# ControlBoardpH.net
KiCad netlist of a schematic drawn in EAGLE
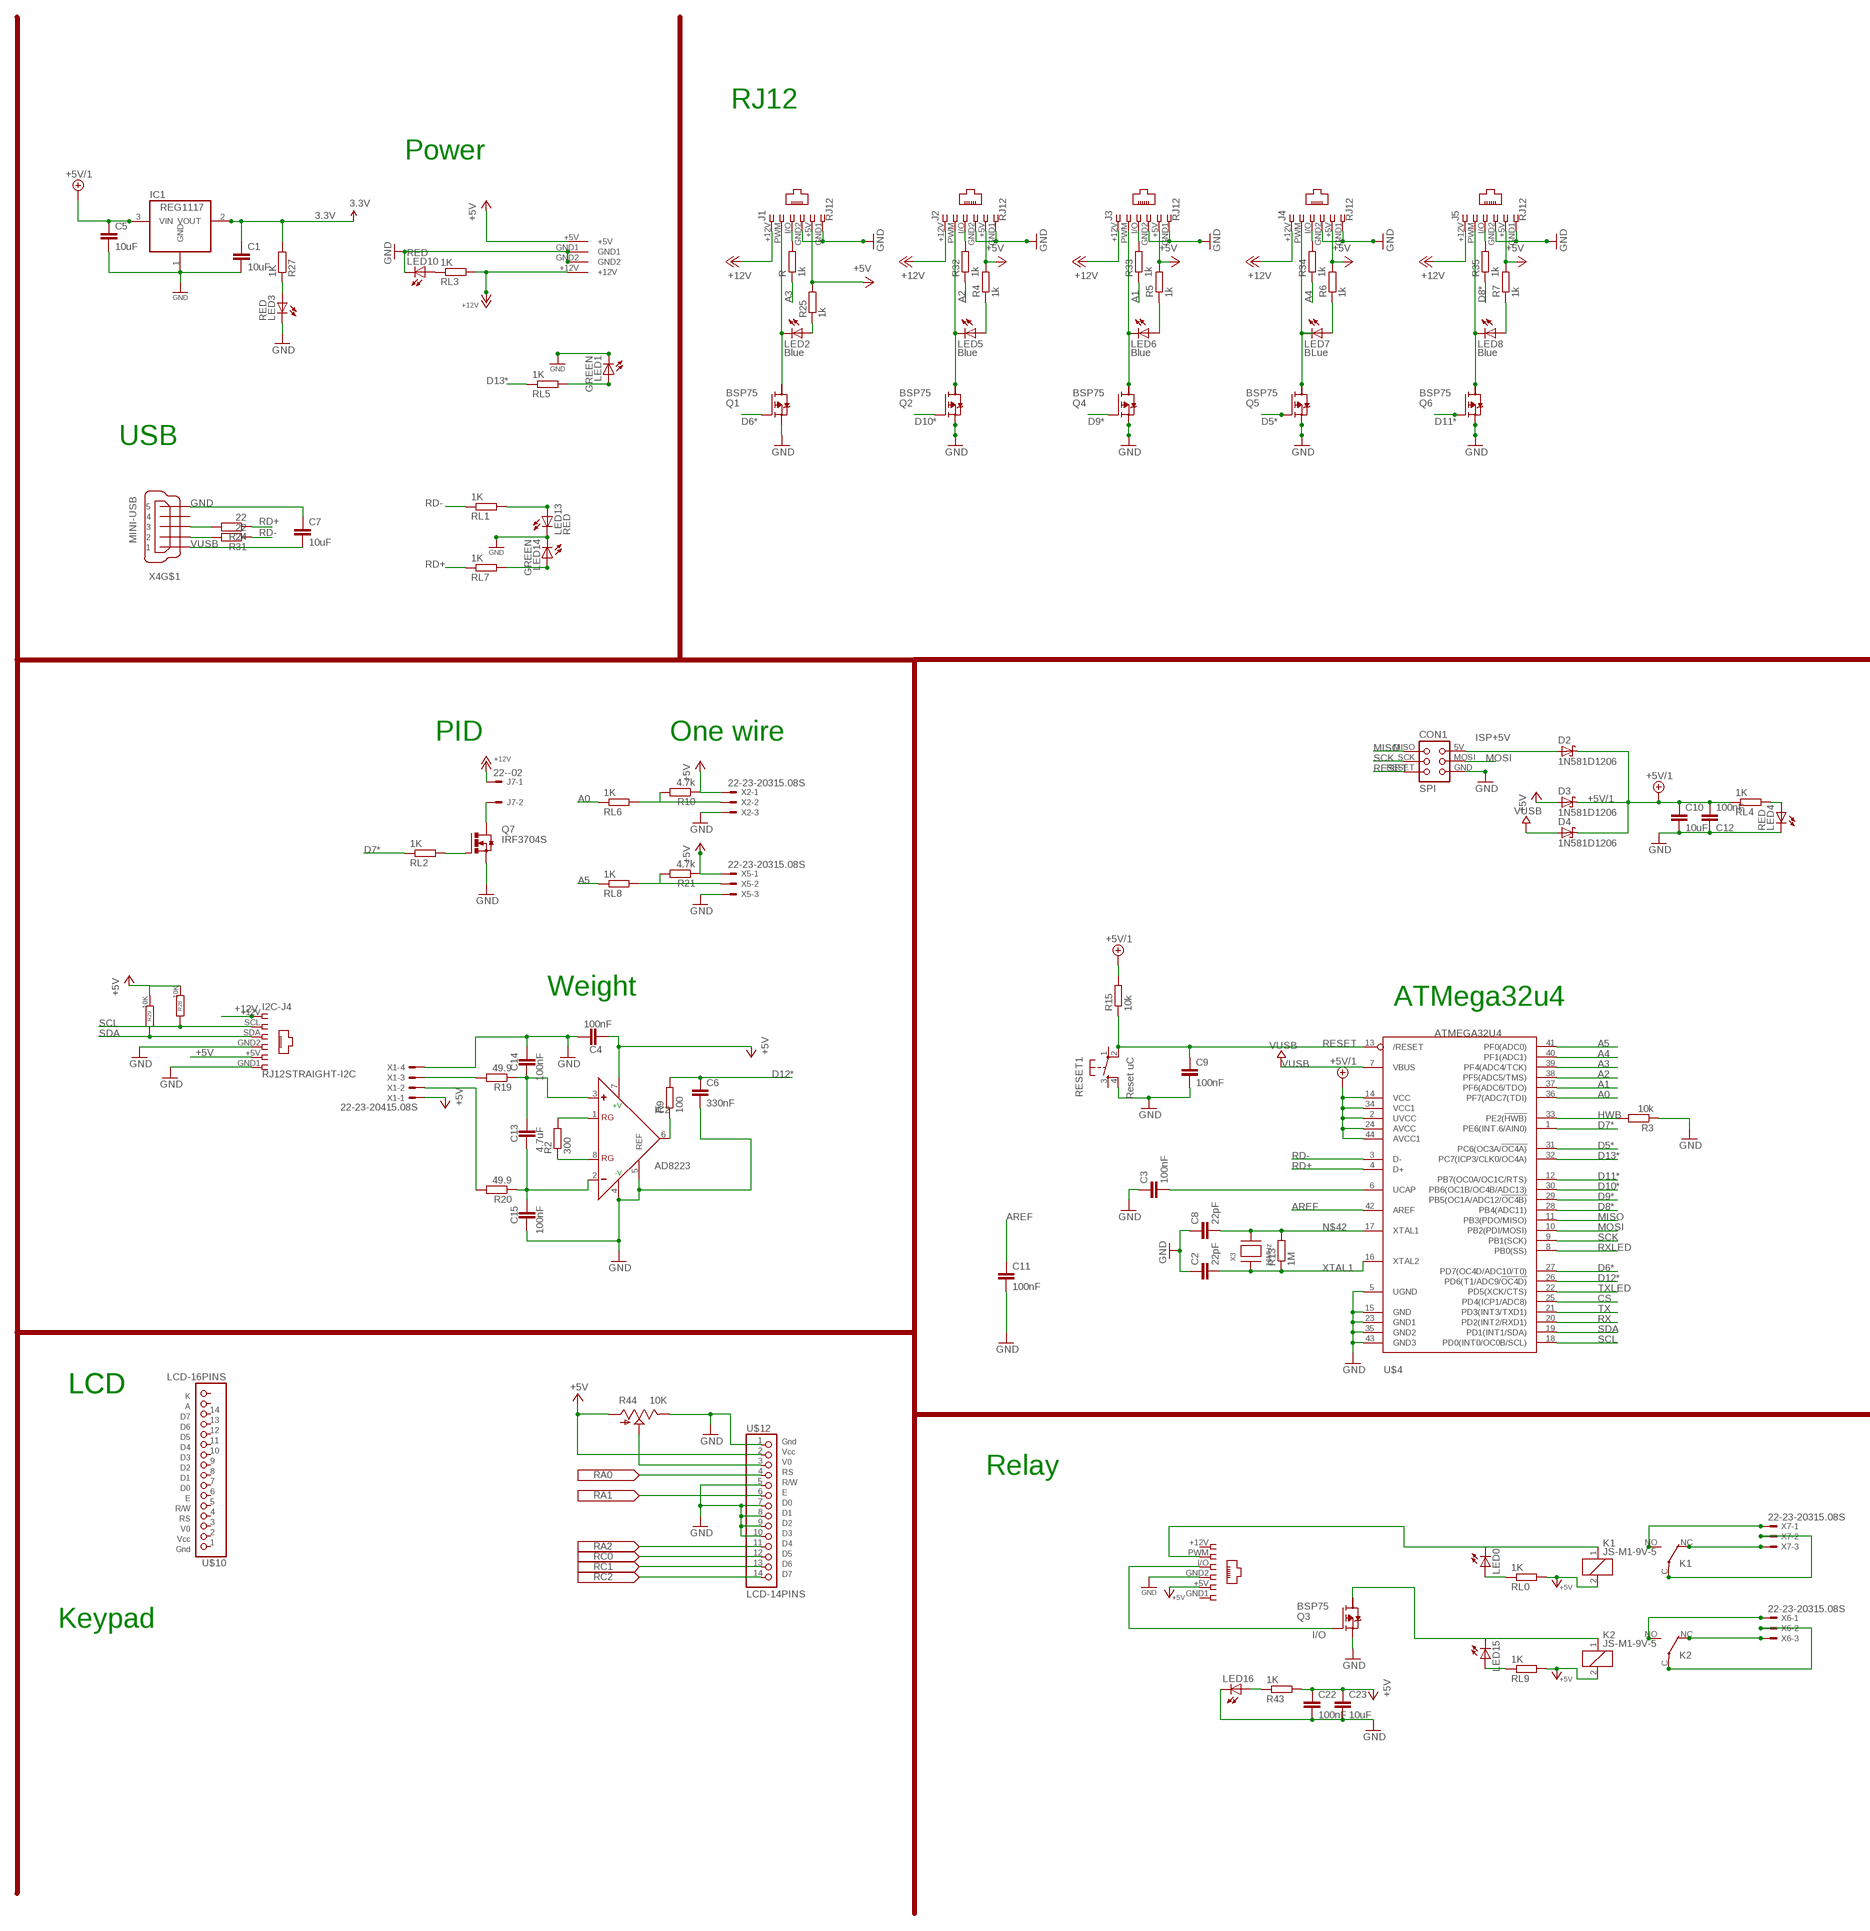
[diagram p0: schematic, sheet 1, part 1 of 2]
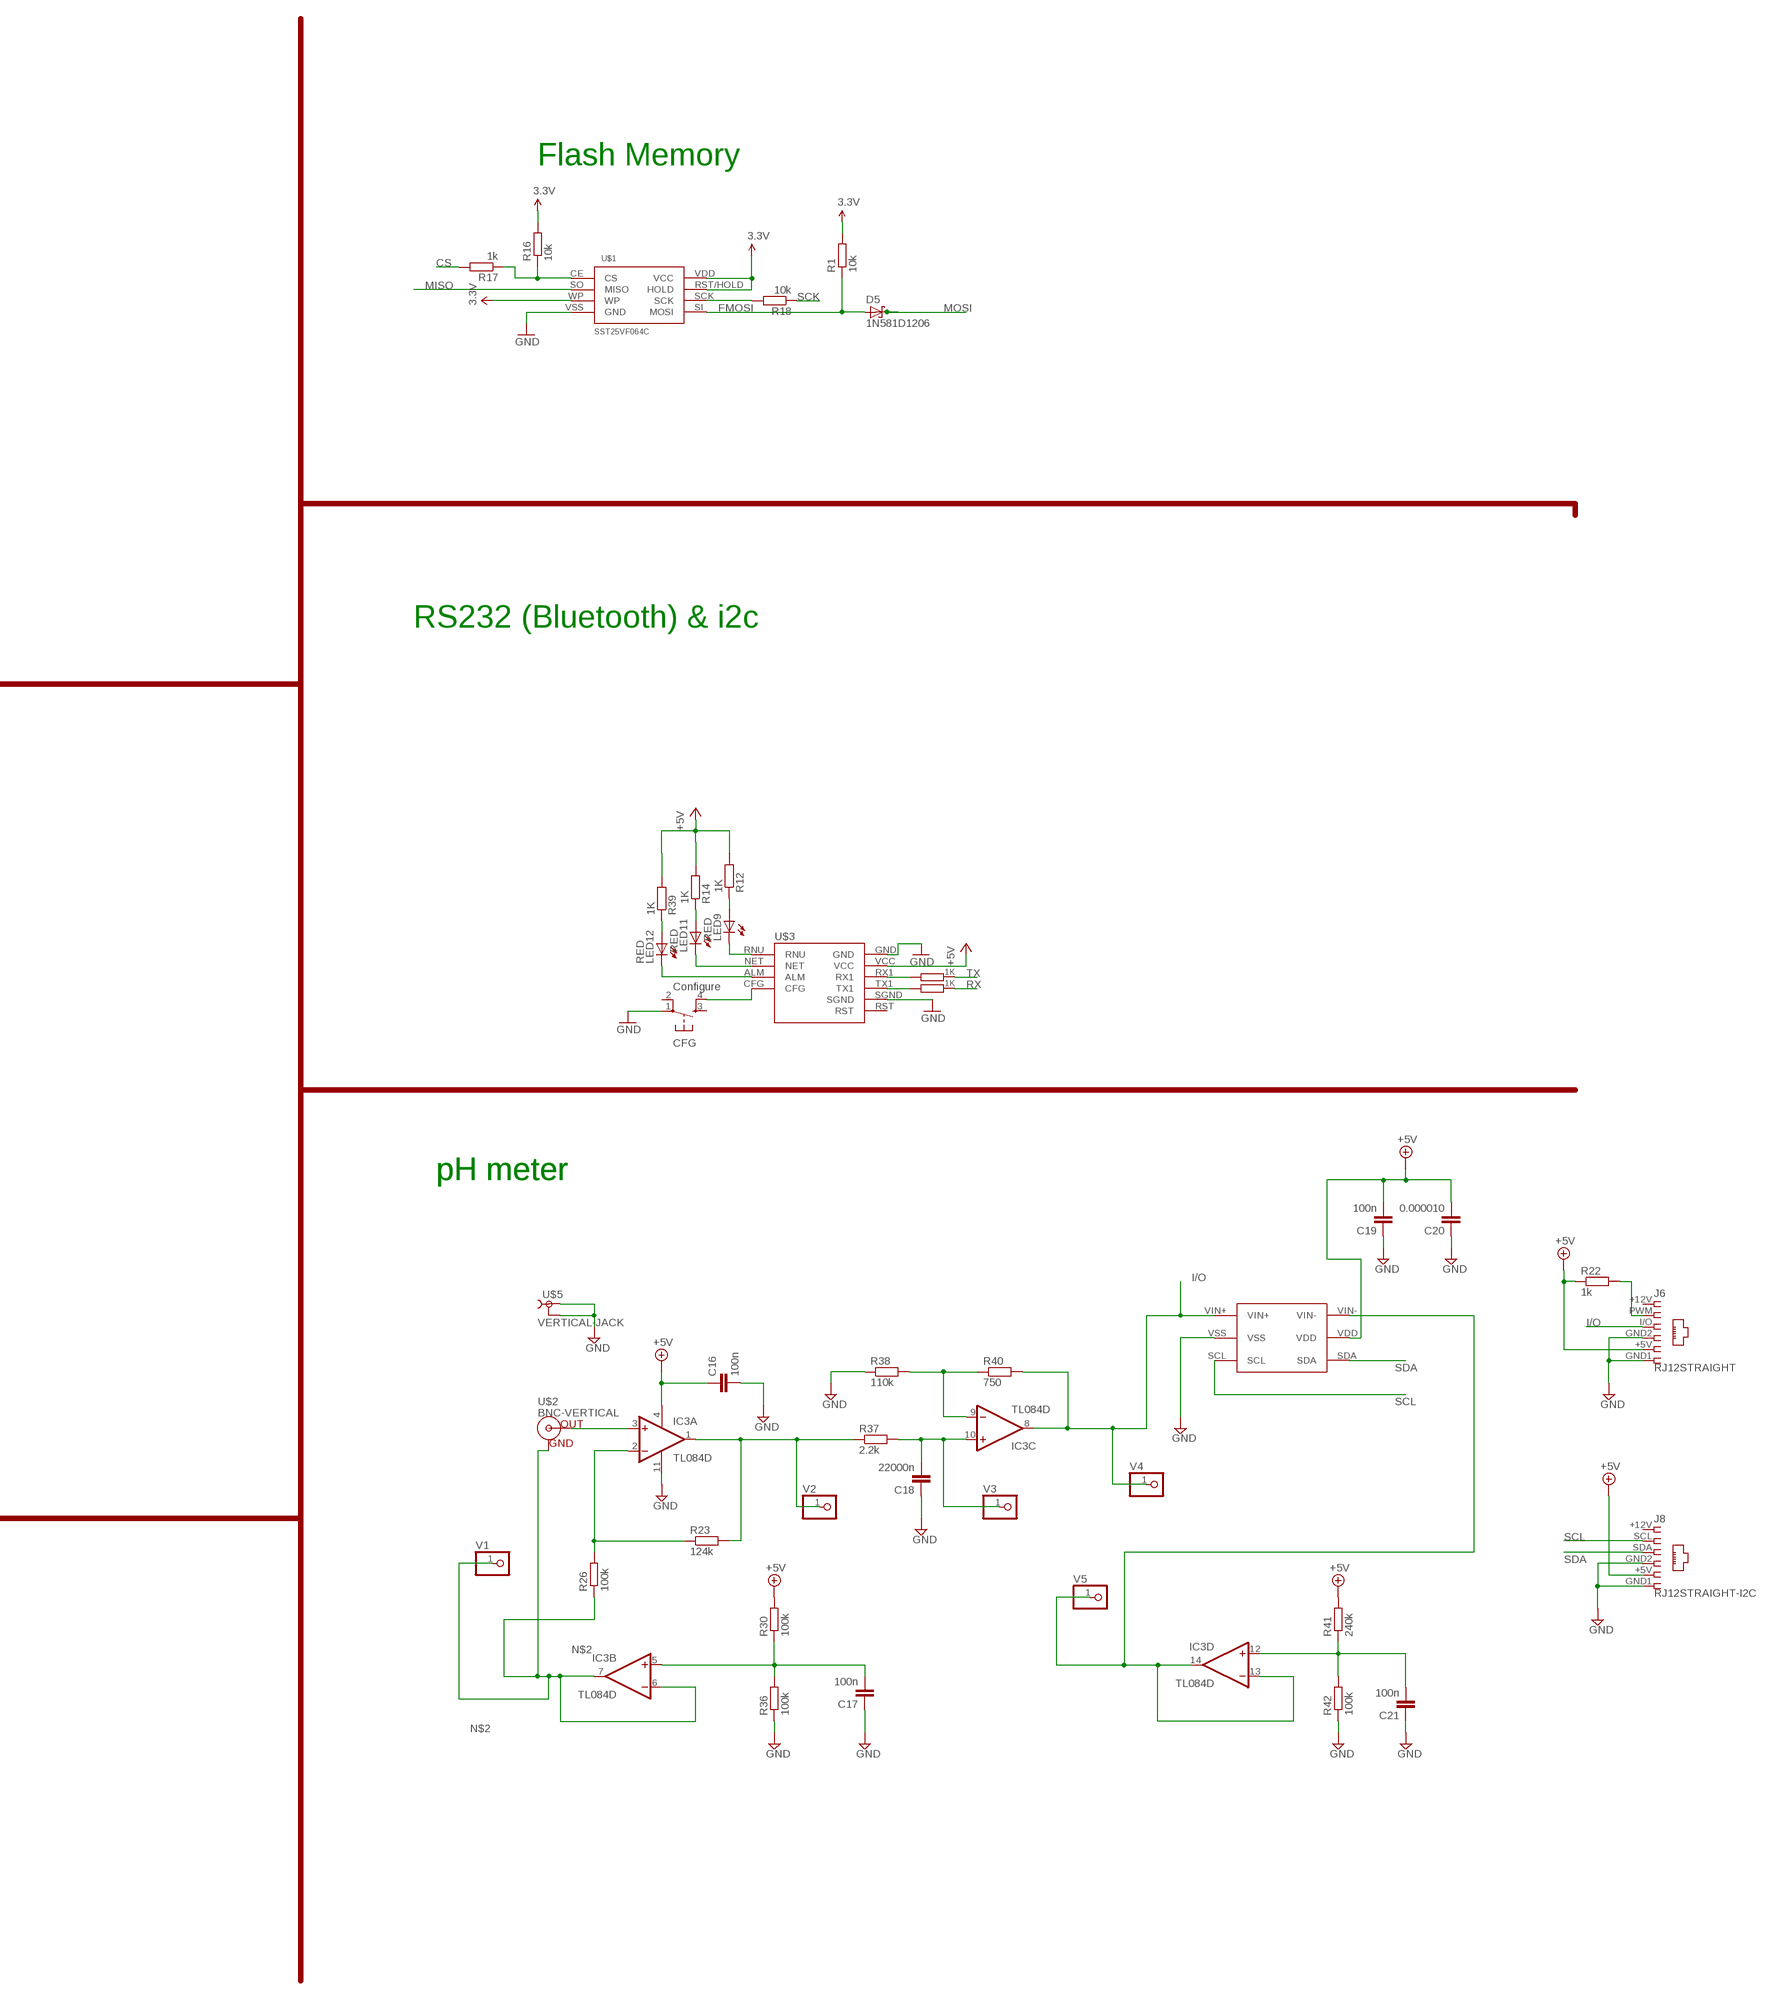
[diagram p1: schematic, sheet 1, part 2 of 2]

(export (version "E")
  (design (tool "Eeschema 10.0.6"))
  (components
    (comp (ref "C1")
      (value "10uF")
      (footprint "eagle-import:C1206")
      (libsource (lib "eagle-import") (part "C-EUC1206"))
    )
    (comp (ref "C2")
      (value "22pF")
      (footprint "eagle-import:C1206")
      (libsource (lib "eagle-import") (part "C-EUC1206"))
    )
    (comp (ref "C3")
      (value "100nF")
      (footprint "eagle-import:C1206")
      (libsource (lib "eagle-import") (part "C-EUC1206"))
    )
    (comp (ref "C4")
      (value "100nF")
      (footprint "eagle-import:C1206")
      (libsource (lib "eagle-import") (part "C-EUC1206"))
    )
    (comp (ref "C5")
      (value "10uF")
      (footprint "eagle-import:C1206")
      (libsource (lib "eagle-import") (part "C-EUC1206"))
    )
    (comp (ref "C6")
      (value "330nF")
      (footprint "eagle-import:C1206")
      (libsource (lib "eagle-import") (part "C-EUC1206"))
    )
    (comp (ref "C7")
      (value "10uF")
      (footprint "eagle-import:C1206")
      (libsource (lib "eagle-import") (part "C-EUC1206"))
    )
    (comp (ref "C8")
      (value "22pF")
      (footprint "eagle-import:C1206")
      (libsource (lib "eagle-import") (part "C-EUC1206"))
    )
    (comp (ref "C9")
      (value "100nF")
      (footprint "eagle-import:C1206")
      (libsource (lib "eagle-import") (part "C-EUC1206"))
    )
    (comp (ref "C10")
      (value "10uF")
      (footprint "eagle-import:C1206")
      (libsource (lib "eagle-import") (part "C-EUC1206"))
    )
    (comp (ref "C11")
      (value "100nF")
      (footprint "eagle-import:C1206")
      (libsource (lib "eagle-import") (part "C-EUC1206"))
    )
    (comp (ref "C12")
      (value "100nF")
      (footprint "eagle-import:C1206")
      (libsource (lib "eagle-import") (part "C-EUC1206"))
    )
    (comp (ref "C13")
      (value "4.7uF")
      (footprint "eagle-import:C1206")
      (libsource (lib "eagle-import") (part "C-EUC1206"))
    )
    (comp (ref "C14")
      (value "100nF")
      (footprint "eagle-import:C1206")
      (libsource (lib "eagle-import") (part "C-EUC1206"))
    )
    (comp (ref "C15")
      (value "100nF")
      (footprint "eagle-import:C1206")
      (libsource (lib "eagle-import") (part "C-EUC1206"))
    )
    (comp (ref "C16")
      (value "100n")
      (footprint "eagle-import:C1206")
      (libsource (lib "eagle-import") (part "C-EUC1206"))
    )
    (comp (ref "C17")
      (value "100n")
      (footprint "eagle-import:C1206")
      (libsource (lib "eagle-import") (part "C-EUC1206"))
    )
    (comp (ref "C18")
      (value "22000n")
      (footprint "eagle-import:C1206")
      (libsource (lib "eagle-import") (part "C-EUC1206"))
    )
    (comp (ref "C19")
      (value "100n")
      (footprint "eagle-import:C1206")
      (libsource (lib "eagle-import") (part "C-EUC1206"))
    )
    (comp (ref "C20")
      (value "0.000010")
      (footprint "eagle-import:C1206")
      (libsource (lib "eagle-import") (part "C-EUC1206"))
    )
    (comp (ref "C21")
      (value "100n")
      (footprint "eagle-import:C1206")
      (libsource (lib "eagle-import") (part "C-EUC1206"))
    )
    (comp (ref "C22")
      (value "100nF")
      (footprint "eagle-import:C1206")
      (libsource (lib "eagle-import") (part "C-EUC1206"))
    )
    (comp (ref "C23")
      (value "10uF")
      (footprint "eagle-import:C1206")
      (libsource (lib "eagle-import") (part "C-EUC1206"))
    )
    (comp (ref "CFG")
      (value "Configure")
      (footprint "eagle-import:TACTILE_SWITCH_SMD")
      (libsource (lib "eagle-import") (part "TAC_SWITCHSMD"))
    )
    (comp (ref "CON1")
      (value "SPI")
      (footprint "eagle-import:TC2030-MCP-NL")
      (libsource (lib "eagle-import") (part "TINYISPT"))
    )
    (comp (ref "D2")
      (value "1N581D1206")
      (footprint "eagle-import:LED-1206")
      (libsource (lib "eagle-import") (part "1N581D1206"))
    )
    (comp (ref "D3")
      (value "1N581D1206")
      (footprint "eagle-import:LED-1206")
      (libsource (lib "eagle-import") (part "1N581D1206"))
    )
    (comp (ref "D4")
      (value "1N581D1206")
      (footprint "eagle-import:LED-1206")
      (libsource (lib "eagle-import") (part "1N581D1206"))
    )
    (comp (ref "D5")
      (value "1N581D1206")
      (footprint "eagle-import:LED-1206")
      (libsource (lib "eagle-import") (part "1N581D1206"))
    )
    (comp (ref "I/O_PWM")
      (value "I2C 1")
      (footprint "eagle-import:RJ12-STRAIGHT")
      (libsource (lib "eagle-import") (part "RJ12STRAIGHT"))
    )
    (comp (ref "I2C-J4")
      (value "RJ12STRAIGHT-I2C")
      (footprint "eagle-import:RJ12-STRAIGHT-I2C")
      (libsource (lib "eagle-import") (part "RJ12STRAIGHT-I2C"))
    )
    (comp (ref "IC1")
      (value "REG1117")
      (footprint "eagle-import:SOT223")
      (libsource (lib "eagle-import") (part "REG1117"))
    )
    (comp (ref "IC2")
      (value "AD8223")
      (footprint "eagle-import:SO8")
      (fields (field (name "MPN") "AD620AR"))
      (libsource (lib "eagle-import") (part "AD620R"))
    )
    (comp (ref "IC3")
      (value "TL084D")
      (footprint "eagle-import:SO14")
      (libsource (lib "eagle-import") (part "TL084D"))
    )
    (comp (ref "J1")
      (value "RJ12")
      (footprint "eagle-import:RJ12-STRAIGHT")
      (libsource (lib "eagle-import") (part "RJ12STRAIGHT"))
    )
    (comp (ref "J2")
      (value "RJ12")
      (footprint "eagle-import:RJ12-STRAIGHT")
      (libsource (lib "eagle-import") (part "RJ12STRAIGHT"))
    )
    (comp (ref "J3")
      (value "RJ12")
      (footprint "eagle-import:RJ12-STRAIGHT")
      (libsource (lib "eagle-import") (part "RJ12STRAIGHT"))
    )
    (comp (ref "J4")
      (value "RJ12")
      (footprint "eagle-import:RJ12-STRAIGHT")
      (libsource (lib "eagle-import") (part "RJ12STRAIGHT"))
    )
    (comp (ref "J5")
      (value "RJ12")
      (footprint "eagle-import:RJ12-STRAIGHT")
      (libsource (lib "eagle-import") (part "RJ12STRAIGHT"))
    )
    (comp (ref "J6")
      (value "RJ12STRAIGHT")
      (footprint "eagle-import:RJ12-STRAIGHT")
      (libsource (lib "eagle-import") (part "RJ12STRAIGHT"))
    )
    (comp (ref "J7")
      (value "22--02")
      (footprint "eagle-import:2-PIN-5.08S")
      (libsource (lib "eagle-import") (part "22-?-02"))
    )
    (comp (ref "J8")
      (value "RJ12STRAIGHT-I2C")
      (footprint "eagle-import:RJ12-STRAIGHT-I2C")
      (libsource (lib "eagle-import") (part "RJ12STRAIGHT-I2C"))
    )
    (comp (ref "K1")
      (value "JS-M1-9V-5")
      (footprint "eagle-import:JS-M")
      (libsource (lib "eagle-import") (part "JS-M1-9V-5"))
    )
    (comp (ref "K2")
      (value "JS-M1-9V-5")
      (footprint "eagle-import:JS-M")
      (libsource (lib "eagle-import") (part "JS-M1-9V-5"))
    )
    (comp (ref "LED0")
      (value "LED1206")
      (footprint "eagle-import:LED-1206")
      (libsource (lib "eagle-import") (part "LED1206"))
    )
    (comp (ref "LED1")
      (value "GREEN")
      (footprint "eagle-import:CHIPLED_1206")
      (libsource (lib "eagle-import") (part "LEDCHIPLED_1206"))
    )
    (comp (ref "LED2")
      (value "Blue")
      (footprint "eagle-import:CHIPLED_1206")
      (libsource (lib "eagle-import") (part "LEDCHIPLED_1206"))
    )
    (comp (ref "LED3")
      (value "RED")
      (footprint "eagle-import:CHIPLED_1206")
      (libsource (lib "eagle-import") (part "LEDCHIPLED_1206"))
    )
    (comp (ref "LED4")
      (value "RED")
      (footprint "eagle-import:CHIPLED_1206")
      (libsource (lib "eagle-import") (part "LEDCHIPLED_1206"))
    )
    (comp (ref "LED5")
      (value "Blue")
      (footprint "eagle-import:CHIPLED_1206")
      (libsource (lib "eagle-import") (part "LEDCHIPLED_1206"))
    )
    (comp (ref "LED6")
      (value "Blue")
      (footprint "eagle-import:CHIPLED_1206")
      (libsource (lib "eagle-import") (part "LEDCHIPLED_1206"))
    )
    (comp (ref "LED7")
      (value "BLue")
      (footprint "eagle-import:CHIPLED_1206")
      (libsource (lib "eagle-import") (part "LEDCHIPLED_1206"))
    )
    (comp (ref "LED8")
      (value "Blue")
      (footprint "eagle-import:CHIPLED_1206")
      (libsource (lib "eagle-import") (part "LEDCHIPLED_1206"))
    )
    (comp (ref "LED9")
      (value "RED")
      (footprint "eagle-import:CHIPLED_1206")
      (libsource (lib "eagle-import") (part "LEDCHIPLED_1206"))
    )
    (comp (ref "LED10")
      (value "RED")
      (footprint "eagle-import:CHIPLED_1206")
      (libsource (lib "eagle-import") (part "LEDCHIPLED_1206"))
    )
    (comp (ref "LED11")
      (value "RED")
      (footprint "eagle-import:CHIPLED_1206")
      (libsource (lib "eagle-import") (part "LEDCHIPLED_1206"))
    )
    (comp (ref "LED12")
      (value "RED")
      (footprint "eagle-import:CHIPLED_1206")
      (libsource (lib "eagle-import") (part "LEDCHIPLED_1206"))
    )
    (comp (ref "LED13")
      (value "RED")
      (footprint "eagle-import:CHIPLED_1206")
      (libsource (lib "eagle-import") (part "LEDCHIPLED_1206"))
    )
    (comp (ref "LED14")
      (value "GREEN")
      (footprint "eagle-import:CHIPLED_1206")
      (libsource (lib "eagle-import") (part "LEDCHIPLED_1206"))
    )
    (comp (ref "LED15")
      (value "LED1206")
      (footprint "eagle-import:LED-1206")
      (libsource (lib "eagle-import") (part "LED1206"))
    )
    (comp (ref "LED16")
      (value "LED1206")
      (footprint "eagle-import:LED-1206")
      (libsource (lib "eagle-import") (part "LED1206"))
    )
    (comp (ref "Q1")
      (value "BSP75")
      (footprint "eagle-import:PG-SOT-223")
      (libsource (lib "eagle-import") (part "BSP613P"))
    )
    (comp (ref "Q2")
      (value "BSP75")
      (footprint "eagle-import:PG-SOT-223")
      (libsource (lib "eagle-import") (part "BSP613P"))
    )
    (comp (ref "Q3")
      (value "BSP75")
      (footprint "eagle-import:PG-SOT-223")
      (libsource (lib "eagle-import") (part "BSP613P"))
    )
    (comp (ref "Q4")
      (value "BSP75")
      (footprint "eagle-import:PG-SOT-223")
      (libsource (lib "eagle-import") (part "BSP613P"))
    )
    (comp (ref "Q5")
      (value "BSP75")
      (footprint "eagle-import:PG-SOT-223")
      (libsource (lib "eagle-import") (part "BSP613P"))
    )
    (comp (ref "Q6")
      (value "BSP75")
      (footprint "eagle-import:PG-SOT-223")
      (libsource (lib "eagle-import") (part "BSP613P"))
    )
    (comp (ref "Q7")
      (value "IRF3704S")
      (footprint "eagle-import:D2PACK")
      (libsource (lib "eagle-import") (part "IRF3704S"))
    )
    (comp (ref "R")
      (value "1k")
      (footprint "eagle-import:R0805")
      (libsource (lib "eagle-import") (part "R-EU_R0805"))
    )
    (comp (ref "R1")
      (value "10k")
      (footprint "eagle-import:R0805")
      (libsource (lib "eagle-import") (part "R-EU_R0805"))
    )
    (comp (ref "R2")
      (value "300")
      (footprint "eagle-import:R1206")
      (libsource (lib "eagle-import") (part "resistor_R-EU_R1206"))
    )
    (comp (ref "R3")
      (value "10k")
      (footprint "eagle-import:M0805")
      (libsource (lib "eagle-import") (part "resistor_R-EU_M0805"))
    )
    (comp (ref "R4")
      (value "1k")
      (footprint "eagle-import:R0805")
      (libsource (lib "eagle-import") (part "R-EU_R0805"))
    )
    (comp (ref "R5")
      (value "1k")
      (footprint "eagle-import:R0805")
      (libsource (lib "eagle-import") (part "R-EU_R0805"))
    )
    (comp (ref "R6")
      (value "1k")
      (footprint "eagle-import:R0805")
      (libsource (lib "eagle-import") (part "R-EU_R0805"))
    )
    (comp (ref "R7")
      (value "1k")
      (footprint "eagle-import:R0805")
      (libsource (lib "eagle-import") (part "R-EU_R0805"))
    )
    (comp (ref "R8")
      (value "1K")
      (footprint "eagle-import:R0805")
      (libsource (lib "eagle-import") (part "R-EU_R0805"))
    )
    (comp (ref "R9")
      (value "100")
      (footprint "eagle-import:R1206")
      (libsource (lib "eagle-import") (part "resistor_R-EU_R1206"))
    )
    (comp (ref "R10")
      (value "4.7k")
      (footprint "eagle-import:R1206")
      (libsource (lib "eagle-import") (part "resistor_R-EU_R1206"))
    )
    (comp (ref "R11")
      (value "1K")
      (footprint "eagle-import:R0805")
      (libsource (lib "eagle-import") (part "R-EU_R0805"))
    )
    (comp (ref "R12")
      (value "1K")
      (footprint "eagle-import:R0805")
      (libsource (lib "eagle-import") (part "R-EU_R0805"))
    )
    (comp (ref "R13")
      (value "1M")
      (footprint "eagle-import:R1206")
      (libsource (lib "eagle-import") (part "R-EU_R1206"))
    )
    (comp (ref "R14")
      (value "1K")
      (footprint "eagle-import:R0805")
      (libsource (lib "eagle-import") (part "R-EU_R0805"))
    )
    (comp (ref "R15")
      (value "10k")
      (footprint "eagle-import:M0805")
      (libsource (lib "eagle-import") (part "resistor_R-EU_M0805"))
    )
    (comp (ref "R16")
      (value "10k")
      (footprint "eagle-import:R0805")
      (libsource (lib "eagle-import") (part "R-EU_R0805"))
    )
    (comp (ref "R17")
      (value "1k")
      (footprint "eagle-import:R0805")
      (libsource (lib "eagle-import") (part "R-EU_R0805"))
    )
    (comp (ref "R18")
      (value "10k")
      (footprint "eagle-import:R0805")
      (libsource (lib "eagle-import") (part "R-EU_R0805"))
    )
    (comp (ref "R19")
      (value "49.9")
      (footprint "eagle-import:R1206")
      (libsource (lib "eagle-import") (part "resistor_R-EU_R1206"))
    )
    (comp (ref "R20")
      (value "49.9")
      (footprint "eagle-import:R1206")
      (libsource (lib "eagle-import") (part "resistor_R-EU_R1206"))
    )
    (comp (ref "R21")
      (value "4.7k")
      (footprint "eagle-import:R1206")
      (libsource (lib "eagle-import") (part "resistor_R-EU_R1206"))
    )
    (comp (ref "R22")
      (value "1k")
      (footprint "eagle-import:R1206")
      (libsource (lib "eagle-import") (part "resistor_R-EU_R1206"))
    )
    (comp (ref "R23")
      (value "124k")
      (footprint "eagle-import:R1206")
      (libsource (lib "eagle-import") (part "resistor_R-EU_R1206"))
    )
    (comp (ref "R24")
      (value "22")
      (footprint "eagle-import:M1206")
      (libsource (lib "eagle-import") (part "resistor_R-EU_M1206"))
    )
    (comp (ref "R25")
      (value "1k")
      (footprint "eagle-import:R0805")
      (libsource (lib "eagle-import") (part "R-EU_R0805"))
    )
    (comp (ref "R26")
      (value "100k")
      (footprint "eagle-import:R1206")
      (libsource (lib "eagle-import") (part "resistor_R-EU_R1206"))
    )
    (comp (ref "R27")
      (value "1K")
      (footprint "eagle-import:R0805")
      (libsource (lib "eagle-import") (part "R-EU_R0805"))
    )
    (comp (ref "R28")
      (value "10K")
      (footprint "eagle-import:M0805")
      (libsource (lib "eagle-import") (part "resistor_R-EU_M0805"))
    )
    (comp (ref "R29")
      (value "10K")
      (footprint "eagle-import:M0805")
      (libsource (lib "eagle-import") (part "resistor_R-EU_M0805"))
    )
    (comp (ref "R30")
      (value "100k")
      (footprint "eagle-import:R1206")
      (libsource (lib "eagle-import") (part "resistor_R-EU_R1206"))
    )
    (comp (ref "R31")
      (value "22")
      (footprint "eagle-import:M1206")
      (libsource (lib "eagle-import") (part "resistor_R-EU_M1206"))
    )
    (comp (ref "R32")
      (value "1k")
      (footprint "eagle-import:R0805")
      (libsource (lib "eagle-import") (part "R-EU_R0805"))
    )
    (comp (ref "R33")
      (value "1k")
      (footprint "eagle-import:R0805")
      (libsource (lib "eagle-import") (part "R-EU_R0805"))
    )
    (comp (ref "R34")
      (value "1k")
      (footprint "eagle-import:R0805")
      (libsource (lib "eagle-import") (part "R-EU_R0805"))
    )
    (comp (ref "R35")
      (value "1k")
      (footprint "eagle-import:R0805")
      (libsource (lib "eagle-import") (part "R-EU_R0805"))
    )
    (comp (ref "R36")
      (value "100k")
      (footprint "eagle-import:R1206")
      (libsource (lib "eagle-import") (part "resistor_R-EU_R1206"))
    )
    (comp (ref "R37")
      (value "2.2k")
      (footprint "eagle-import:R1206")
      (libsource (lib "eagle-import") (part "resistor_R-EU_R1206"))
    )
    (comp (ref "R38")
      (value "110k")
      (footprint "eagle-import:R1206")
      (libsource (lib "eagle-import") (part "resistor_R-EU_R1206"))
    )
    (comp (ref "R39")
      (value "1K")
      (footprint "eagle-import:R0805")
      (libsource (lib "eagle-import") (part "R-EU_R0805"))
    )
    (comp (ref "R40")
      (value "750")
      (footprint "eagle-import:R1206")
      (libsource (lib "eagle-import") (part "resistor_R-EU_R1206"))
    )
    (comp (ref "R41")
      (value "240k")
      (footprint "eagle-import:R1206")
      (libsource (lib "eagle-import") (part "resistor_R-EU_R1206"))
    )
    (comp (ref "R42")
      (value "100k")
      (footprint "eagle-import:R1206")
      (libsource (lib "eagle-import") (part "resistor_R-EU_R1206"))
    )
    (comp (ref "R43")
      (value "1K")
      (footprint "eagle-import:M1206")
      (libsource (lib "eagle-import") (part "resistor_R-EU_M1206"))
    )
    (comp (ref "R44")
      (value "10K")
      (footprint "eagle-import:ECP10S")
      (libsource (lib "eagle-import") (part "TRIM_US-ECP10S"))
    )
    (comp (ref "RESET1")
      (value "Reset uC")
      (footprint "eagle-import:TACTILE_SWITCH_SMD")
      (libsource (lib "eagle-import") (part "TAC_SWITCHSMD"))
    )
    (comp (ref "RL0")
      (value "1K")
      (footprint "eagle-import:M1206")
      (libsource (lib "eagle-import") (part "resistor_R-EU_M1206"))
    )
    (comp (ref "RL1")
      (value "1K")
      (footprint "eagle-import:R0805")
      (libsource (lib "eagle-import") (part "R-EU_R0805"))
    )
    (comp (ref "RL2")
      (value "1K")
      (footprint "eagle-import:R0805")
      (libsource (lib "eagle-import") (part "R-EU_R0805"))
    )
    (comp (ref "RL3")
      (value "1K")
      (footprint "eagle-import:R0805")
      (libsource (lib "eagle-import") (part "R-EU_R0805"))
    )
    (comp (ref "RL4")
      (value "1K")
      (footprint "eagle-import:R0805")
      (libsource (lib "eagle-import") (part "resistor_R-EU_R0805"))
    )
    (comp (ref "RL5")
      (value "1K")
      (footprint "eagle-import:R0805")
      (libsource (lib "eagle-import") (part "R-EU_R0805"))
    )
    (comp (ref "RL6")
      (value "1K")
      (footprint "eagle-import:R0805")
      (libsource (lib "eagle-import") (part "R-EU_R0805"))
    )
    (comp (ref "RL7")
      (value "1K")
      (footprint "eagle-import:R0805")
      (libsource (lib "eagle-import") (part "R-EU_R0805"))
    )
    (comp (ref "RL8")
      (value "1K")
      (footprint "eagle-import:R0805")
      (libsource (lib "eagle-import") (part "R-EU_R0805"))
    )
    (comp (ref "RL9")
      (value "1K")
      (footprint "eagle-import:M1206")
      (libsource (lib "eagle-import") (part "resistor_R-EU_M1206"))
    )
    (comp (ref "U$1")
      (value "SST25VF064C")
      (footprint "eagle-import:SOIC_8-LEAD")
      (libsource (lib "eagle-import") (part "SST25VF064C"))
    )
    (comp (ref "U$2")
      (value "BNC-VERTICAL")
      (footprint "eagle-import:BNC-VERTICAL")
      (libsource (lib "eagle-import") (part "BNC-VERTICAL"))
    )
    (comp (ref "U$3")
      (value "SZ05-ZIGBEE")
      (footprint "eagle-import:SZ05-ZIGBEE")
      (libsource (lib "eagle-import") (part "SZ05-ZIGBEE"))
    )
    (comp (ref "U$4")
      (value "ATMEGA32U4")
      (footprint "eagle-import:TQFP44")
      (libsource (lib "eagle-import") (part "ATMEGA32U4-AU"))
    )
    (comp (ref "U$5")
      (value "VERTICAL-JACK")
      (footprint "eagle-import:VERTICAL-JACK")
      (libsource (lib "eagle-import") (part "VERTICAL-JACK"))
    )
    (comp (ref "U$6")
      (value "KPJX-4S-S")
      (footprint "eagle-import:KPJX-4S-S")
      (libsource (lib "eagle-import") (part "KPJX-4S-S"))
    )
    (comp (ref "U$9")
      (value "MCP3425")
      (footprint "eagle-import:SOT-23-6")
      (libsource (lib "eagle-import") (part "MCP3425"))
    )
    (comp (ref "U$10")
      (value "LCD-16PINS")
      (footprint "eagle-import:LCD-16PINS")
      (libsource (lib "eagle-import") (part "LCD-16PINS"))
    )
    (comp (ref "U$12")
      (value "LCD-14PINS")
      (footprint "eagle-import:LCD-14PINS")
      (libsource (lib "eagle-import") (part "LCD-14PINS"))
    )
    (comp (ref "V1")
      (value "PINHD-1X1")
      (footprint "eagle-import:1X01")
      (libsource (lib "eagle-import") (part "PINHD-1X1"))
    )
    (comp (ref "V2")
      (value "PINHD-1X1")
      (footprint "eagle-import:1X01")
      (libsource (lib "eagle-import") (part "PINHD-1X1"))
    )
    (comp (ref "V3")
      (value "PINHD-1X1")
      (footprint "eagle-import:1X01")
      (libsource (lib "eagle-import") (part "PINHD-1X1"))
    )
    (comp (ref "V4")
      (value "PINHD-1X1")
      (footprint "eagle-import:1X01")
      (libsource (lib "eagle-import") (part "PINHD-1X1"))
    )
    (comp (ref "V5")
      (value "PINHD-1X1")
      (footprint "eagle-import:1X01")
      (libsource (lib "eagle-import") (part "PINHD-1X1"))
    )
    (comp (ref "X1")
      (value "22-23-20415.08S")
      (footprint "eagle-import:4-PIN-5.08S")
      (libsource (lib "eagle-import") (part "22-23-20415.08S"))
    )
    (comp (ref "X2")
      (value "22-23-20315.08S")
      (footprint "eagle-import:3-PIN-5.08S")
      (libsource (lib "eagle-import") (part "22-23-20315.08S"))
    )
    (comp (ref "X3")
      (value "16MHz")
      (footprint "eagle-import:NX6035")
      (libsource (lib "eagle-import") (part "XTALNX6035"))
    )
    (comp (ref "X4")
      (value "MINI-USB")
      (footprint "eagle-import:32005-201")
      (libsource (lib "eagle-import") (part "MINI-USB-SCHIELD-32005-201"))
    )
    (comp (ref "X5")
      (value "22-23-20315.08S")
      (footprint "eagle-import:3-PIN-5.08S")
      (libsource (lib "eagle-import") (part "22-23-20315.08S"))
    )
    (comp (ref "X6")
      (value "22-23-20315.08S")
      (footprint "eagle-import:3-PIN-5.08S")
      (libsource (lib "eagle-import") (part "22-23-20315.08S"))
    )
    (comp (ref "X7")
      (value "22-23-20315.08S")
      (footprint "eagle-import:3-PIN-5.08S")
      (libsource (lib "eagle-import") (part "22-23-20315.08S"))
    )
  )
  (nets
    (net (code "1") (name "+5V") (class "Default")
      (node (ref "C16") (pin "1") (pinfunction "1_1") (pintype "passive"))
      (node (ref "C19") (pin "2") (pinfunction "2_2") (pintype "passive"))
      (node (ref "C20") (pin "2") (pinfunction "2_2") (pintype "passive"))
      (node (ref "C22") (pin "1") (pinfunction "1_1") (pintype "passive"))
      (node (ref "C23") (pin "1") (pinfunction "1_1") (pintype "passive"))
      (node (ref "C4") (pin "2") (pinfunction "2_2") (pintype "passive"))
      (node (ref "D3") (pin "A") (pinfunction "A_A") (pintype "passive"))
      (node (ref "I/O_PWM") (pin "+5V") (pinfunction "5_+5V") (pintype "bidirectional"))
      (node (ref "I2C-J4") (pin "+5V") (pinfunction "5_+5V") (pintype "bidirectional"))
      (node (ref "IC2") (pin "7") (pinfunction "+V_7") (pintype "power_in"))
      (node (ref "IC3") (pin "4") (pinfunction "V+_4") (pintype "power_in"))
      (node (ref "J1") (pin "+5V") (pinfunction "5_+5V") (pintype "bidirectional"))
      (node (ref "J2") (pin "+5V") (pinfunction "5_+5V") (pintype "bidirectional"))
      (node (ref "J3") (pin "+5V") (pinfunction "5_+5V") (pintype "bidirectional"))
      (node (ref "J4") (pin "+5V") (pinfunction "5_+5V") (pintype "bidirectional"))
      (node (ref "J5") (pin "+5V") (pinfunction "5_+5V") (pintype "bidirectional"))
      (node (ref "J6") (pin "+5V") (pinfunction "5_+5V") (pintype "bidirectional"))
      (node (ref "J8") (pin "+5V") (pinfunction "5_+5V") (pintype "bidirectional"))
      (node (ref "K1") (pin "2") (pinfunction "2_2") (pintype "passive"))
      (node (ref "K2") (pin "2") (pinfunction "2_2") (pintype "passive"))
      (node (ref "R10") (pin "1") (pinfunction "1_1") (pintype "passive"))
      (node (ref "R12") (pin "2") (pinfunction "2_2") (pintype "passive"))
      (node (ref "R14") (pin "2") (pinfunction "2_2") (pintype "passive"))
      (node (ref "R21") (pin "1") (pinfunction "1_1") (pintype "passive"))
      (node (ref "R22") (pin "1") (pinfunction "1_1") (pintype "passive"))
      (node (ref "R25") (pin "2") (pinfunction "2_2") (pintype "passive"))
      (node (ref "R28") (pin "1") (pinfunction "1_1") (pintype "passive"))
      (node (ref "R29") (pin "1") (pinfunction "1_1") (pintype "passive"))
      (node (ref "R30") (pin "2") (pinfunction "2_2") (pintype "passive"))
      (node (ref "R39") (pin "2") (pinfunction "2_2") (pintype "passive"))
      (node (ref "R4") (pin "2") (pinfunction "2_2") (pintype "passive"))
      (node (ref "R41") (pin "2") (pinfunction "2_2") (pintype "passive"))
      (node (ref "R43") (pin "2") (pinfunction "2_2") (pintype "passive"))
      (node (ref "R44") (pin "A") (pinfunction "A_A") (pintype "passive"))
      (node (ref "R5") (pin "2") (pinfunction "2_2") (pintype "passive"))
      (node (ref "R6") (pin "2") (pinfunction "2_2") (pintype "passive"))
      (node (ref "R7") (pin "2") (pinfunction "2_2") (pintype "passive"))
      (node (ref "RL0") (pin "2") (pinfunction "2_2") (pintype "passive"))
      (node (ref "RL9") (pin "2") (pinfunction "2_2") (pintype "passive"))
      (node (ref "U$12") (pin "2") (pinfunction "2_2") (pintype "passive"))
      (node (ref "U$3") (pin "VCC") (pinfunction "VCC_VCC") (pintype "bidirectional"))
      (node (ref "U$6") (pin "+5V") (pinfunction "+5V_+5V") (pintype "power_in"))
      (node (ref "U$9") (pin "VDD") (pinfunction "VDD_VDD") (pintype "bidirectional"))
      (node (ref "X1") (pin "1") (pinfunction "S_1") (pintype "passive"))
      (node (ref "X2") (pin "1") (pinfunction "S_1") (pintype "passive"))
      (node (ref "X5") (pin "1") (pinfunction "S_1") (pintype "passive"))
    )
    (net (code "2") (name "+5V{slash}1") (class "Default")
      (node (ref "C10") (pin "1") (pinfunction "1_1") (pintype "passive"))
      (node (ref "C12") (pin "2") (pinfunction "2_2") (pintype "passive"))
      (node (ref "C5") (pin "1") (pinfunction "1_1") (pintype "passive"))
      (node (ref "D2") (pin "C") (pinfunction "C_C") (pintype "passive"))
      (node (ref "D3") (pin "C") (pinfunction "C_C") (pintype "passive"))
      (node (ref "D4") (pin "C") (pinfunction "C_C") (pintype "passive"))
      (node (ref "IC1") (pin "3") (pinfunction "VIN_3") (pintype "input"))
      (node (ref "R15") (pin "2") (pinfunction "2_2") (pintype "passive"))
      (node (ref "RL4") (pin "1") (pinfunction "1_1") (pintype "passive"))
      (node (ref "U$4") (pin "14") (pinfunction "VCC_14") (pintype "bidirectional"))
      (node (ref "U$4") (pin "2") (pinfunction "UVCC_2") (pintype "bidirectional"))
      (node (ref "U$4") (pin "24") (pinfunction "AVCC_24") (pintype "bidirectional"))
      (node (ref "U$4") (pin "34") (pinfunction "VCC1_34") (pintype "bidirectional"))
      (node (ref "U$4") (pin "44") (pinfunction "AVCC1_44") (pintype "bidirectional"))
    )
    (net (code "3") (name "+12V") (class "Default")
      (node (ref "I2C-J4") (pin "+12V") (pinfunction "1_+12V") (pintype "bidirectional"))
      (node (ref "J1") (pin "+12V") (pinfunction "1_+12V") (pintype "bidirectional"))
      (node (ref "J2") (pin "+12V") (pinfunction "1_+12V") (pintype "bidirectional"))
      (node (ref "J3") (pin "+12V") (pinfunction "1_+12V") (pintype "bidirectional"))
      (node (ref "J4") (pin "+12V") (pinfunction "1_+12V") (pintype "bidirectional"))
      (node (ref "J5") (pin "+12V") (pinfunction "1_+12V") (pintype "bidirectional"))
      (node (ref "J7") (pin "1") (pinfunction "S_1") (pintype "passive"))
      (node (ref "RL3") (pin "2") (pinfunction "2_2") (pintype "passive"))
      (node (ref "U$6") (pin "+12V") (pinfunction "+12V_+12V") (pintype "power_in"))
    )
    (net (code "4") (name "/A0") (class "Default")
      (node (ref "RL6") (pin "1") (pinfunction "1_1") (pintype "passive"))
      (node (ref "U$4") (pin "36") (pinfunction "PF7(ADC7(TDI)_36") (pintype "bidirectional"))
    )
    (net (code "5") (name "/A1") (class "Default")
      (node (ref "R33") (pin "1") (pinfunction "1_1") (pintype "passive"))
      (node (ref "U$4") (pin "37") (pinfunction "PF6(ADC6/TDO)_37") (pintype "bidirectional"))
    )
    (net (code "6") (name "/A2") (class "Default")
      (node (ref "R32") (pin "1") (pinfunction "1_1") (pintype "passive"))
      (node (ref "U$4") (pin "38") (pinfunction "PF5(ADC5/TMS)_38") (pintype "bidirectional"))
    )
    (net (code "7") (name "/A3") (class "Default")
      (node (ref "R") (pin "1") (pinfunction "1_1") (pintype "passive"))
      (node (ref "U$4") (pin "39") (pinfunction "PF4(ADC4/TCK)_39") (pintype "bidirectional"))
    )
    (net (code "8") (name "/A4") (class "Default")
      (node (ref "R34") (pin "1") (pinfunction "1_1") (pintype "passive"))
      (node (ref "U$4") (pin "40") (pinfunction "PF1(ADC1)_40") (pintype "bidirectional"))
    )
    (net (code "9") (name "/A5") (class "Default")
      (node (ref "RL8") (pin "1") (pinfunction "1_1") (pintype "passive"))
      (node (ref "U$4") (pin "41") (pinfunction "PF0(ADC0)_41") (pintype "bidirectional"))
    )
    (net (code "10") (name "/AREF") (class "Default")
      (node (ref "C11") (pin "1") (pinfunction "1_1") (pintype "passive"))
      (node (ref "U$4") (pin "42") (pinfunction "AREF_42") (pintype "bidirectional"))
    )
    (net (code "11") (name "/CS") (class "Default")
      (node (ref "R17") (pin "2") (pinfunction "2_2") (pintype "passive"))
      (node (ref "U$4") (pin "25") (pinfunction "PD4(ICP1/ADC8)_25") (pintype "bidirectional"))
    )
    (net (code "12") (name "/D5*") (class "Default")
      (node (ref "Q5") (pin "1") (pinfunction "G_1") (pintype "passive"))
      (node (ref "U$4") (pin "31") (pinfunction "PC6(OC3A/~{OC4A})_31") (pintype "bidirectional"))
    )
    (net (code "13") (name "/D6*") (class "Default")
      (node (ref "Q1") (pin "1") (pinfunction "G_1") (pintype "passive"))
      (node (ref "U$4") (pin "27") (pinfunction "PD7(OC4D/ADC10/T0)_27") (pintype "bidirectional"))
    )
    (net (code "14") (name "/D7*") (class "Default")
      (node (ref "RL2") (pin "1") (pinfunction "1_1") (pintype "passive"))
      (node (ref "U$4") (pin "1") (pinfunction "PE6(INT.6/AIN0)_1") (pintype "bidirectional"))
    )
    (net (code "15") (name "/D8*") (class "Default")
      (node (ref "R35") (pin "1") (pinfunction "1_1") (pintype "passive"))
      (node (ref "U$4") (pin "28") (pinfunction "PB4(ADC11)_28") (pintype "bidirectional"))
    )
    (net (code "16") (name "/D9*") (class "Default")
      (node (ref "Q4") (pin "1") (pinfunction "G_1") (pintype "passive"))
      (node (ref "U$4") (pin "29") (pinfunction "PB5(OC1A/ADC12/~{OC4B})_29") (pintype "bidirectional"))
    )
    (net (code "17") (name "/D10*") (class "Default")
      (node (ref "Q2") (pin "1") (pinfunction "G_1") (pintype "passive"))
      (node (ref "U$4") (pin "30") (pinfunction "PB6(OC1B/OC4B/ADC13)_30") (pintype "bidirectional"))
    )
    (net (code "18") (name "/D11*") (class "Default")
      (node (ref "Q6") (pin "1") (pinfunction "G_1") (pintype "passive"))
      (node (ref "U$4") (pin "12") (pinfunction "PB7(OC0A/OC1C/RTS)_12") (pintype "bidirectional"))
    )
    (net (code "19") (name "/D12*") (class "Default")
      (node (ref "C6") (pin "1") (pinfunction "1_1") (pintype "passive"))
      (node (ref "R9") (pin "2") (pinfunction "2_2") (pintype "passive"))
      (node (ref "U$4") (pin "26") (pinfunction "PD6(T1/ADC9/~{OC4D})_26") (pintype "bidirectional"))
    )
    (net (code "20") (name "/D13*") (class "Default")
      (node (ref "RL5") (pin "1") (pinfunction "1_1") (pintype "passive"))
      (node (ref "U$4") (pin "32") (pinfunction "PC7(ICP3/CLK0/OC4A)_32") (pintype "bidirectional"))
    )
    (net (code "21") (name "/FMOSI") (class "Default")
      (node (ref "D5") (pin "A") (pinfunction "A_A") (pintype "passive"))
      (node (ref "R1") (pin "1") (pinfunction "1_1") (pintype "passive"))
      (node (ref "U$1") (pin "SI") (pinfunction "MOSI_SI") (pintype "bidirectional"))
    )
    (net (code "22") (name "/HWB") (class "Default")
      (node (ref "R3") (pin "2") (pinfunction "2_2") (pintype "passive"))
      (node (ref "U$4") (pin "33") (pinfunction "PE2(~{HWB})_33") (pintype "bidirectional"))
    )
    (net (code "23") (name "/ISP+5V") (class "Default")
      (node (ref "CON1") (pin "5V") (pinfunction "VCC_5V") (pintype "passive"))
      (node (ref "D2") (pin "A") (pinfunction "A_A") (pintype "passive"))
    )
    (net (code "24") (name "/I{slash}O") (class "Default")
      (node (ref "I/O_PWM") (pin "I/O") (pinfunction "3_I/O") (pintype "bidirectional"))
      (node (ref "IC3") (pin "8") (pinfunction "OUT_8") (pintype "output"))
      (node (ref "J6") (pin "I/O") (pinfunction "3_I/O") (pintype "bidirectional"))
      (node (ref "Q3") (pin "1") (pinfunction "G_1") (pintype "passive"))
      (node (ref "R40") (pin "2") (pinfunction "2_2") (pintype "passive"))
      (node (ref "U$9") (pin "VIN+") (pinfunction "VIN+_VIN+") (pintype "bidirectional"))
      (node (ref "V4") (pin "1") (pinfunction "1_1") (pintype "passive"))
    )
    (net (code "25") (name "/MISO") (class "Default")
      (node (ref "CON1") (pin "MISO") (pinfunction "MISO_MISO") (pintype "passive"))
      (node (ref "U$1") (pin "SO") (pinfunction "MISO_SO") (pintype "bidirectional"))
      (node (ref "U$4") (pin "11") (pinfunction "PB3(PDO/MISO)_11") (pintype "bidirectional"))
    )
    (net (code "26") (name "/MOSI") (class "Default")
      (node (ref "CON1") (pin "MOSI") (pinfunction "MOSI_MOSI") (pintype "passive"))
      (node (ref "D5") (pin "C") (pinfunction "C_C") (pintype "passive"))
      (node (ref "U$4") (pin "10") (pinfunction "PB2(PDI/MOSI)_10") (pintype "bidirectional"))
    )
    (net (code "27") (name "/N$2") (class "Default")
      (node (ref "IC3") (pin "6") (pinfunction "-IN_6") (pintype "input"))
      (node (ref "IC3") (pin "7") (pinfunction "OUT_7") (pintype "output"))
      (node (ref "J2") (pin "I/O") (pinfunction "3_I/O") (pintype "bidirectional"))
      (node (ref "R26") (pin "1") (pinfunction "1_1") (pintype "passive"))
      (node (ref "R32") (pin "2") (pinfunction "2_2") (pintype "passive"))
      (node (ref "U$2") (pin "G") (pinfunction "GND_G") (pintype "bidirectional"))
      (node (ref "V1") (pin "1") (pinfunction "1_1") (pintype "passive"))
    )
    (net (code "28") (name "/N$42") (class "Default")
      (node (ref "C8") (pin "2") (pinfunction "2_2") (pintype "passive"))
      (node (ref "R13") (pin "2") (pinfunction "2_2") (pintype "passive"))
      (node (ref "U$4") (pin "17") (pinfunction "XTAL1_17") (pintype "bidirectional"))
      (node (ref "X3") (pin "P$2") (pinfunction "P$2_P$2") (pintype "bidirectional"))
    )
    (net (code "29") (name "/RD+") (class "Default")
      (node (ref "R24") (pin "1") (pinfunction "1_1") (pintype "passive"))
      (node (ref "RL7") (pin "1") (pinfunction "1_1") (pintype "passive"))
      (node (ref "U$4") (pin "4") (pinfunction "D+_4") (pintype "bidirectional"))
    )
    (net (code "30") (name "/RD-") (class "Default")
      (node (ref "R31") (pin "1") (pinfunction "1_1") (pintype "passive"))
      (node (ref "RL1") (pin "1") (pinfunction "1_1") (pintype "passive"))
      (node (ref "U$4") (pin "3") (pinfunction "D-_3") (pintype "bidirectional"))
    )
    (net (code "31") (name "/RESET") (class "Default")
      (node (ref "C9") (pin "1") (pinfunction "1_1") (pintype "passive"))
      (node (ref "CON1") (pin "RESET") (pinfunction "RESET_RESET") (pintype "passive"))
      (node (ref "R15") (pin "1") (pinfunction "1_1") (pintype "passive"))
      (node (ref "RESET1") (pin "2") (pinfunction "2_2") (pintype "passive"))
      (node (ref "U$4") (pin "13") (pinfunction "/RESET_13") (pintype "bidirectional"))
    )
    (net (code "32") (name "/RX") (class "Default")
      (node (ref "R8") (pin "1") (pinfunction "1_1") (pintype "passive"))
      (node (ref "U$4") (pin "20") (pinfunction "PD2(INT2/RXD1)_20") (pintype "bidirectional"))
    )
    (net (code "33") (name "/RXLED") (class "Default")
      (node (ref "U$4") (pin "8") (pinfunction "PB0(SS)_8") (pintype "bidirectional"))
    )
    (net (code "34") (name "/SCK") (class "Default")
      (node (ref "CON1") (pin "SCK") (pinfunction "SCK_SCK") (pintype "passive"))
      (node (ref "R18") (pin "1") (pinfunction "1_1") (pintype "passive"))
      (node (ref "U$4") (pin "9") (pinfunction "PB1(SCK)_9") (pintype "bidirectional"))
    )
    (net (code "35") (name "/SCL") (class "Default")
      (node (ref "I2C-J4") (pin "SCL") (pinfunction "2_SCL") (pintype "bidirectional"))
      (node (ref "J8") (pin "SCL") (pinfunction "2_SCL") (pintype "bidirectional"))
      (node (ref "R28") (pin "2") (pinfunction "2_2") (pintype "passive"))
      (node (ref "U$4") (pin "18") (pinfunction "PD0(INT0/OC0B/SCL)_18") (pintype "bidirectional"))
      (node (ref "U$9") (pin "SCL") (pinfunction "SCL_SCL") (pintype "bidirectional"))
    )
    (net (code "36") (name "/SDA") (class "Default")
      (node (ref "I2C-J4") (pin "SDA") (pinfunction "3_SDA") (pintype "bidirectional"))
      (node (ref "J8") (pin "SDA") (pinfunction "3_SDA") (pintype "bidirectional"))
      (node (ref "R29") (pin "2") (pinfunction "2_2") (pintype "passive"))
      (node (ref "U$4") (pin "19") (pinfunction "PD1(INT1/SDA)_19") (pintype "bidirectional"))
      (node (ref "U$9") (pin "SDA") (pinfunction "SDA_SDA") (pintype "bidirectional"))
    )
    (net (code "37") (name "/TX") (class "Default")
      (node (ref "R11") (pin "1") (pinfunction "1_1") (pintype "passive"))
      (node (ref "U$4") (pin "21") (pinfunction "PD3(INT3/TXD1)_21") (pintype "bidirectional"))
    )
    (net (code "38") (name "/TXLED") (class "Default")
      (node (ref "U$4") (pin "22") (pinfunction "PD5(XCK/CTS)_22") (pintype "bidirectional"))
    )
    (net (code "39") (name "/XTAL1") (class "Default")
      (node (ref "C2") (pin "2") (pinfunction "2_2") (pintype "passive"))
      (node (ref "R13") (pin "1") (pinfunction "1_1") (pintype "passive"))
      (node (ref "U$4") (pin "16") (pinfunction "XTAL2_16") (pintype "bidirectional"))
      (node (ref "X3") (pin "P$1") (pinfunction "P$1_P$1") (pintype "bidirectional"))
    )
    (net (code "40") (name "3.3V") (class "Default")
      (node (ref "C1") (pin "1") (pinfunction "1_1") (pintype "passive"))
      (node (ref "IC1") (pin "2") (pinfunction "VOUT_2") (pintype "output"))
      (node (ref "R1") (pin "2") (pinfunction "2_2") (pintype "passive"))
      (node (ref "R16") (pin "2") (pinfunction "2_2") (pintype "passive"))
      (node (ref "R27") (pin "2") (pinfunction "2_2") (pintype "passive"))
      (node (ref "U$1") (pin "RST/HOLD") (pinfunction "HOLD_RST/HOLD") (pintype "bidirectional"))
      (node (ref "U$1") (pin "VDD") (pinfunction "VCC_VDD") (pintype "bidirectional"))
      (node (ref "U$1") (pin "WP") (pinfunction "WP_WP") (pintype "bidirectional"))
    )
    (net (code "41") (name "GND") (class "Default")
      (node (ref "C1") (pin "2") (pinfunction "2_2") (pintype "passive"))
      (node (ref "C10") (pin "2") (pinfunction "2_2") (pintype "passive"))
      (node (ref "C11") (pin "2") (pinfunction "2_2") (pintype "passive"))
      (node (ref "C12") (pin "1") (pinfunction "1_1") (pintype "passive"))
      (node (ref "C14") (pin "1") (pinfunction "1_1") (pintype "passive"))
      (node (ref "C15") (pin "2") (pinfunction "2_2") (pintype "passive"))
      (node (ref "C16") (pin "2") (pinfunction "2_2") (pintype "passive"))
      (node (ref "C17") (pin "1") (pinfunction "1_1") (pintype "passive"))
      (node (ref "C18") (pin "1") (pinfunction "1_1") (pintype "passive"))
      (node (ref "C19") (pin "1") (pinfunction "1_1") (pintype "passive"))
      (node (ref "C2") (pin "1") (pinfunction "1_1") (pintype "passive"))
      (node (ref "C20") (pin "1") (pinfunction "1_1") (pintype "passive"))
      (node (ref "C21") (pin "1") (pinfunction "1_1") (pintype "passive"))
      (node (ref "C22") (pin "2") (pinfunction "2_2") (pintype "passive"))
      (node (ref "C23") (pin "2") (pinfunction "2_2") (pintype "passive"))
      (node (ref "C3") (pin "1") (pinfunction "1_1") (pintype "passive"))
      (node (ref "C4") (pin "1") (pinfunction "1_1") (pintype "passive"))
      (node (ref "C5") (pin "2") (pinfunction "2_2") (pintype "passive"))
      (node (ref "C6") (pin "2") (pinfunction "2_2") (pintype "passive"))
      (node (ref "C7") (pin "1") (pinfunction "1_1") (pintype "passive"))
      (node (ref "C8") (pin "1") (pinfunction "1_1") (pintype "passive"))
      (node (ref "C9") (pin "2") (pinfunction "2_2") (pintype "passive"))
      (node (ref "CFG") (pin "1") (pinfunction "1_1") (pintype "passive"))
      (node (ref "CON1") (pin "GND") (pinfunction "GND_GND") (pintype "passive"))
      (node (ref "I/O_PWM") (pin "GND2") (pinfunction "4_GND2") (pintype "bidirectional"))
      (node (ref "I2C-J4") (pin "GND1") (pinfunction "6_GND1") (pintype "bidirectional"))
      (node (ref "I2C-J4") (pin "GND2") (pinfunction "4_GND2") (pintype "bidirectional"))
      (node (ref "IC1") (pin "1") (pinfunction "GND_1") (pintype "power_in"))
      (node (ref "IC2") (pin "4") (pinfunction "-V_4") (pintype "power_in"))
      (node (ref "IC2") (pin "5") (pinfunction "REF_5") (pintype "passive"))
      (node (ref "IC3") (pin "11") (pinfunction "V-_11") (pintype "power_in"))
      (node (ref "J1") (pin "GND1") (pinfunction "6_GND1") (pintype "bidirectional"))
      (node (ref "J1") (pin "GND2") (pinfunction "4_GND2") (pintype "bidirectional"))
      (node (ref "J2") (pin "GND1") (pinfunction "6_GND1") (pintype "bidirectional"))
      (node (ref "J2") (pin "GND2") (pinfunction "4_GND2") (pintype "bidirectional"))
      (node (ref "J3") (pin "GND1") (pinfunction "6_GND1") (pintype "bidirectional"))
      (node (ref "J3") (pin "GND2") (pinfunction "4_GND2") (pintype "bidirectional"))
      (node (ref "J4") (pin "GND1") (pinfunction "6_GND1") (pintype "bidirectional"))
      (node (ref "J4") (pin "GND2") (pinfunction "4_GND2") (pintype "bidirectional"))
      (node (ref "J5") (pin "GND1") (pinfunction "6_GND1") (pintype "bidirectional"))
      (node (ref "J5") (pin "GND2") (pinfunction "4_GND2") (pintype "bidirectional"))
      (node (ref "J6") (pin "GND1") (pinfunction "6_GND1") (pintype "bidirectional"))
      (node (ref "J6") (pin "GND2") (pinfunction "4_GND2") (pintype "bidirectional"))
      (node (ref "J8") (pin "GND1") (pinfunction "6_GND1") (pintype "bidirectional"))
      (node (ref "J8") (pin "GND2") (pinfunction "4_GND2") (pintype "bidirectional"))
      (node (ref "LED1") (pin "C") (pinfunction "C_C") (pintype "passive"))
      (node (ref "LED10") (pin "C") (pinfunction "C_C") (pintype "passive"))
      (node (ref "LED13") (pin "C") (pinfunction "C_C") (pintype "passive"))
      (node (ref "LED14") (pin "C") (pinfunction "C_C") (pintype "passive"))
      (node (ref "LED16") (pin "C") (pinfunction "C_C") (pintype "passive"))
      (node (ref "LED3") (pin "C") (pinfunction "C_C") (pintype "passive"))
      (node (ref "LED4") (pin "C") (pinfunction "C_C") (pintype "passive"))
      (node (ref "Q1") (pin "3") (pinfunction "S_3") (pintype "passive"))
      (node (ref "Q2") (pin "3") (pinfunction "S_3") (pintype "passive"))
      (node (ref "Q3") (pin "3") (pinfunction "S_3") (pintype "passive"))
      (node (ref "Q4") (pin "3") (pinfunction "S_3") (pintype "passive"))
      (node (ref "Q5") (pin "3") (pinfunction "S_3") (pintype "passive"))
      (node (ref "Q6") (pin "3") (pinfunction "S_3") (pintype "passive"))
      (node (ref "Q7") (pin "3") (pinfunction "S_3") (pintype "passive"))
      (node (ref "R3") (pin "1") (pinfunction "1_1") (pintype "passive"))
      (node (ref "R36") (pin "1") (pinfunction "1_1") (pintype "passive"))
      (node (ref "R38") (pin "1") (pinfunction "1_1") (pintype "passive"))
      (node (ref "R42") (pin "1") (pinfunction "1_1") (pintype "passive"))
      (node (ref "R44") (pin "E") (pinfunction "E_E") (pintype "passive"))
      (node (ref "RESET1") (pin "4") (pinfunction "4_4") (pintype "passive"))
      (node (ref "U$1") (pin "VSS") (pinfunction "GND_VSS") (pintype "bidirectional"))
      (node (ref "U$12") (pin "1") (pinfunction "1_1") (pintype "passive"))
      (node (ref "U$12") (pin "10") (pinfunction "10_10") (pintype "passive"))
      (node (ref "U$12") (pin "5") (pinfunction "5_5") (pintype "passive"))
      (node (ref "U$12") (pin "7") (pinfunction "7_7") (pintype "passive"))
      (node (ref "U$12") (pin "8") (pinfunction "8_8") (pintype "passive"))
      (node (ref "U$12") (pin "9") (pinfunction "9_9") (pintype "passive"))
      (node (ref "U$3") (pin "GND") (pinfunction "GND_GND") (pintype "bidirectional"))
      (node (ref "U$3") (pin "SGND") (pinfunction "SGND_SGND") (pintype "bidirectional"))
      (node (ref "U$4") (pin "15") (pinfunction "GND_15") (pintype "bidirectional"))
      (node (ref "U$4") (pin "23") (pinfunction "GND1_23") (pintype "bidirectional"))
      (node (ref "U$4") (pin "35") (pinfunction "GND2_35") (pintype "bidirectional"))
      (node (ref "U$4") (pin "43") (pinfunction "GND3_43") (pintype "bidirectional"))
      (node (ref "U$4") (pin "5") (pinfunction "UGND_5") (pintype "bidirectional"))
      (node (ref "U$5") (pin "P$1") (pinfunction "1_P$1") (pintype "passive"))
      (node (ref "U$5") (pin "P$2") (pinfunction "2_P$2") (pintype "passive"))
      (node (ref "U$6") (pin "GND1") (pinfunction "GND1_GND1") (pintype "input"))
      (node (ref "U$6") (pin "GND2") (pinfunction "GND2_GND2") (pintype "input"))
      (node (ref "U$9") (pin "VSS") (pinfunction "VSS_VSS") (pintype "bidirectional"))
      (node (ref "X1") (pin "4") (pinfunction "S_4") (pintype "passive"))
      (node (ref "X2") (pin "3") (pinfunction "S_3") (pintype "passive"))
      (node (ref "X4") (pin "5") (pinfunction "5_5") (pintype "passive"))
      (node (ref "X5") (pin "3") (pinfunction "S_3") (pintype "passive"))
    )
    (net (code "42") (name "Net-(CFG-Pad4)") (class "Default")
      (node (ref "CFG") (pin "4") (pinfunction "4_4") (pintype "passive"))
      (node (ref "U$3") (pin "CFG") (pinfunction "CFG_CFG") (pintype "bidirectional"))
    )
    (net (code "43") (name "Net-(I/O_PWM-2)") (class "Default")
      (node (ref "I/O_PWM") (pin "PWM") (pinfunction "2_PWM") (pintype "bidirectional"))
      (node (ref "K1") (pin "1") (pinfunction "1_1") (pintype "passive"))
      (node (ref "LED0") (pin "C") (pinfunction "C_C") (pintype "passive"))
    )
    (net (code "44") (name "Net-(IC2-+)") (class "Default")
      (node (ref "C13") (pin "1") (pinfunction "1_1") (pintype "passive"))
      (node (ref "C14") (pin "2") (pinfunction "2_2") (pintype "passive"))
      (node (ref "IC2") (pin "3") (pinfunction "+_3") (pintype "input"))
      (node (ref "R19") (pin "1") (pinfunction "1_1") (pintype "passive"))
    )
    (net (code "45") (name "Net-(IC2--)") (class "Default")
      (node (ref "C13") (pin "2") (pinfunction "2_2") (pintype "passive"))
      (node (ref "C15") (pin "1") (pinfunction "1_1") (pintype "passive"))
      (node (ref "IC2") (pin "2") (pinfunction "-_2") (pintype "input"))
      (node (ref "R20") (pin "1") (pinfunction "1_1") (pintype "passive"))
    )
    (net (code "46") (name "Net-(IC2-OUT)") (class "Default")
      (node (ref "IC2") (pin "6") (pinfunction "OUT_6") (pintype "output"))
      (node (ref "R9") (pin "1") (pinfunction "1_1") (pintype "passive"))
    )
    (net (code "47") (name "Net-(IC2-RG-Pad1)") (class "Default")
      (node (ref "IC2") (pin "1") (pinfunction "RG_1") (pintype "passive"))
      (node (ref "R2") (pin "2") (pinfunction "2_2") (pintype "passive"))
    )
    (net (code "48") (name "Net-(IC2-RG-Pad8)") (class "Default")
      (node (ref "IC2") (pin "8") (pinfunction "RG_8") (pintype "passive"))
      (node (ref "R2") (pin "1") (pinfunction "1_1") (pintype "passive"))
    )
    (net (code "49") (name "Net-(IC3A-+IN)") (class "Default")
      (node (ref "IC3") (pin "3") (pinfunction "+IN_3") (pintype "input"))
      (node (ref "U$2") (pin "S") (pinfunction "OUT_S") (pintype "bidirectional"))
    )
    (net (code "50") (name "Net-(IC3A--IN)") (class "Default")
      (node (ref "IC3") (pin "2") (pinfunction "-IN_2") (pintype "input"))
      (node (ref "R23") (pin "1") (pinfunction "1_1") (pintype "passive"))
      (node (ref "R26") (pin "2") (pinfunction "2_2") (pintype "passive"))
    )
    (net (code "51") (name "Net-(IC3A-OUT)") (class "Default")
      (node (ref "IC3") (pin "1") (pinfunction "OUT_1") (pintype "output"))
      (node (ref "R23") (pin "2") (pinfunction "2_2") (pintype "passive"))
      (node (ref "R37") (pin "1") (pinfunction "1_1") (pintype "passive"))
      (node (ref "V2") (pin "1") (pinfunction "1_1") (pintype "passive"))
    )
    (net (code "52") (name "Net-(IC3B-+IN)") (class "Default")
      (node (ref "C17") (pin "2") (pinfunction "2_2") (pintype "passive"))
      (node (ref "IC3") (pin "5") (pinfunction "+IN_5") (pintype "input"))
      (node (ref "R30") (pin "1") (pinfunction "1_1") (pintype "passive"))
      (node (ref "R36") (pin "2") (pinfunction "2_2") (pintype "passive"))
    )
    (net (code "53") (name "Net-(IC3C-+IN)") (class "Default")
      (node (ref "C18") (pin "2") (pinfunction "2_2") (pintype "passive"))
      (node (ref "IC3") (pin "10") (pinfunction "+IN_10") (pintype "input"))
      (node (ref "R37") (pin "2") (pinfunction "2_2") (pintype "passive"))
      (node (ref "V3") (pin "1") (pinfunction "1_1") (pintype "passive"))
    )
    (net (code "54") (name "Net-(IC3C--IN)") (class "Default")
      (node (ref "IC3") (pin "9") (pinfunction "-IN_9") (pintype "input"))
      (node (ref "R38") (pin "2") (pinfunction "2_2") (pintype "passive"))
      (node (ref "R40") (pin "1") (pinfunction "1_1") (pintype "passive"))
    )
    (net (code "55") (name "Net-(IC3D-+IN)") (class "Default")
      (node (ref "C21") (pin "2") (pinfunction "2_2") (pintype "passive"))
      (node (ref "IC3") (pin "12") (pinfunction "+IN_12") (pintype "input"))
      (node (ref "R41") (pin "1") (pinfunction "1_1") (pintype "passive"))
      (node (ref "R42") (pin "2") (pinfunction "2_2") (pintype "passive"))
    )
    (net (code "56") (name "Net-(IC3D--IN)") (class "Default")
      (node (ref "IC3") (pin "13") (pinfunction "-IN_13") (pintype "input"))
      (node (ref "IC3") (pin "14") (pinfunction "OUT_14") (pintype "output"))
      (node (ref "U$9") (pin "VIN-") (pinfunction "VIN-_VIN-") (pintype "bidirectional"))
      (node (ref "V5") (pin "1") (pinfunction "1_1") (pintype "passive"))
    )
    (net (code "57") (name "Net-(J1-2)") (class "Default")
      (node (ref "J1") (pin "PWM") (pinfunction "2_PWM") (pintype "bidirectional"))
      (node (ref "LED2") (pin "C") (pinfunction "C_C") (pintype "passive"))
      (node (ref "Q1") (pin "2") (pinfunction "D_2") (pintype "passive"))
    )
    (net (code "58") (name "Net-(J1-3)") (class "Default")
      (node (ref "J1") (pin "I/O") (pinfunction "3_I/O") (pintype "bidirectional"))
      (node (ref "R") (pin "2") (pinfunction "2_2") (pintype "passive"))
    )
    (net (code "59") (name "Net-(J2-2)") (class "Default")
      (node (ref "J2") (pin "PWM") (pinfunction "2_PWM") (pintype "bidirectional"))
      (node (ref "LED5") (pin "C") (pinfunction "C_C") (pintype "passive"))
      (node (ref "Q2") (pin "2") (pinfunction "D_2") (pintype "passive"))
    )
    (net (code "60") (name "Net-(J3-2)") (class "Default")
      (node (ref "J3") (pin "PWM") (pinfunction "2_PWM") (pintype "bidirectional"))
      (node (ref "LED6") (pin "C") (pinfunction "C_C") (pintype "passive"))
      (node (ref "Q4") (pin "2") (pinfunction "D_2") (pintype "passive"))
    )
    (net (code "61") (name "Net-(J3-3)") (class "Default")
      (node (ref "J3") (pin "I/O") (pinfunction "3_I/O") (pintype "bidirectional"))
      (node (ref "R33") (pin "2") (pinfunction "2_2") (pintype "passive"))
    )
    (net (code "62") (name "Net-(J4-2)") (class "Default")
      (node (ref "J4") (pin "PWM") (pinfunction "2_PWM") (pintype "bidirectional"))
      (node (ref "LED7") (pin "C") (pinfunction "C_C") (pintype "passive"))
      (node (ref "Q5") (pin "2") (pinfunction "D_2") (pintype "passive"))
    )
    (net (code "63") (name "Net-(J4-3)") (class "Default")
      (node (ref "J4") (pin "I/O") (pinfunction "3_I/O") (pintype "bidirectional"))
      (node (ref "R34") (pin "2") (pinfunction "2_2") (pintype "passive"))
    )
    (net (code "64") (name "Net-(J5-2)") (class "Default")
      (node (ref "J5") (pin "PWM") (pinfunction "2_PWM") (pintype "bidirectional"))
      (node (ref "LED8") (pin "C") (pinfunction "C_C") (pintype "passive"))
      (node (ref "Q6") (pin "2") (pinfunction "D_2") (pintype "passive"))
    )
    (net (code "65") (name "Net-(J5-3)") (class "Default")
      (node (ref "J5") (pin "I/O") (pinfunction "3_I/O") (pintype "bidirectional"))
      (node (ref "R35") (pin "2") (pinfunction "2_2") (pintype "passive"))
    )
    (net (code "66") (name "Net-(J6-2)") (class "Default")
      (node (ref "J6") (pin "PWM") (pinfunction "2_PWM") (pintype "bidirectional"))
      (node (ref "R22") (pin "2") (pinfunction "2_2") (pintype "passive"))
    )
    (net (code "67") (name "Net-(J7B-S)") (class "Default")
      (node (ref "J7") (pin "2") (pinfunction "S_2") (pintype "passive"))
      (node (ref "Q7") (pin "2") (pinfunction "D_2") (pintype "passive"))
    )
    (net (code "68") (name "Net-(K1B-O)") (class "Default")
      (node (ref "K1") (pin "NC") (pinfunction "O_NC") (pintype "passive"))
      (node (ref "X7") (pin "3") (pinfunction "S_3") (pintype "passive"))
    )
    (net (code "69") (name "Net-(K1B-P)") (class "Default")
      (node (ref "K1") (pin "C") (pinfunction "P_C") (pintype "passive"))
      (node (ref "X7") (pin "2") (pinfunction "S_2") (pintype "passive"))
    )
    (net (code "70") (name "Net-(K1B-S)") (class "Default")
      (node (ref "K1") (pin "NO") (pinfunction "S_NO") (pintype "passive"))
      (node (ref "X7") (pin "1") (pinfunction "S_1") (pintype "passive"))
    )
    (net (code "71") (name "Net-(K2-Pad1)") (class "Default")
      (node (ref "K2") (pin "1") (pinfunction "1_1") (pintype "passive"))
      (node (ref "LED15") (pin "C") (pinfunction "C_C") (pintype "passive"))
      (node (ref "Q3") (pin "2") (pinfunction "D_2") (pintype "passive"))
    )
    (net (code "72") (name "Net-(K2B-O)") (class "Default")
      (node (ref "K2") (pin "NC") (pinfunction "O_NC") (pintype "passive"))
      (node (ref "X6") (pin "3") (pinfunction "S_3") (pintype "passive"))
    )
    (net (code "73") (name "Net-(K2B-P)") (class "Default")
      (node (ref "K2") (pin "C") (pinfunction "P_C") (pintype "passive"))
      (node (ref "X6") (pin "2") (pinfunction "S_2") (pintype "passive"))
    )
    (net (code "74") (name "Net-(K2B-S)") (class "Default")
      (node (ref "K2") (pin "NO") (pinfunction "S_NO") (pintype "passive"))
      (node (ref "X6") (pin "1") (pinfunction "S_1") (pintype "passive"))
    )
    (net (code "75") (name "Net-(LED0-PadA)") (class "Default")
      (node (ref "LED0") (pin "A") (pinfunction "A_A") (pintype "passive"))
      (node (ref "RL0") (pin "1") (pinfunction "1_1") (pintype "passive"))
    )
    (net (code "76") (name "Net-(LED1-PadA)") (class "Default")
      (node (ref "LED1") (pin "A") (pinfunction "A_A") (pintype "passive"))
      (node (ref "RL5") (pin "2") (pinfunction "2_2") (pintype "passive"))
    )
    (net (code "77") (name "Net-(LED2-PadA)") (class "Default")
      (node (ref "LED2") (pin "A") (pinfunction "A_A") (pintype "passive"))
      (node (ref "R25") (pin "1") (pinfunction "1_1") (pintype "passive"))
    )
    (net (code "78") (name "Net-(LED3-PadA)") (class "Default")
      (node (ref "LED3") (pin "A") (pinfunction "A_A") (pintype "passive"))
      (node (ref "R27") (pin "1") (pinfunction "1_1") (pintype "passive"))
    )
    (net (code "79") (name "Net-(LED4-PadA)") (class "Default")
      (node (ref "LED4") (pin "A") (pinfunction "A_A") (pintype "passive"))
      (node (ref "RL4") (pin "2") (pinfunction "2_2") (pintype "passive"))
    )
    (net (code "80") (name "Net-(LED5-PadA)") (class "Default")
      (node (ref "LED5") (pin "A") (pinfunction "A_A") (pintype "passive"))
      (node (ref "R4") (pin "1") (pinfunction "1_1") (pintype "passive"))
    )
    (net (code "81") (name "Net-(LED6-PadA)") (class "Default")
      (node (ref "LED6") (pin "A") (pinfunction "A_A") (pintype "passive"))
      (node (ref "R5") (pin "1") (pinfunction "1_1") (pintype "passive"))
    )
    (net (code "82") (name "Net-(LED7-PadA)") (class "Default")
      (node (ref "LED7") (pin "A") (pinfunction "A_A") (pintype "passive"))
      (node (ref "R6") (pin "1") (pinfunction "1_1") (pintype "passive"))
    )
    (net (code "83") (name "Net-(LED8-PadA)") (class "Default")
      (node (ref "LED8") (pin "A") (pinfunction "A_A") (pintype "passive"))
      (node (ref "R7") (pin "1") (pinfunction "1_1") (pintype "passive"))
    )
    (net (code "84") (name "Net-(LED9-PadA)") (class "Default")
      (node (ref "LED9") (pin "A") (pinfunction "A_A") (pintype "passive"))
      (node (ref "R12") (pin "1") (pinfunction "1_1") (pintype "passive"))
    )
    (net (code "85") (name "Net-(LED9-PadC)") (class "Default")
      (node (ref "LED9") (pin "C") (pinfunction "C_C") (pintype "passive"))
      (node (ref "U$3") (pin "RNU") (pinfunction "RNU_RNU") (pintype "bidirectional"))
    )
    (net (code "86") (name "Net-(LED10-PadA)") (class "Default")
      (node (ref "LED10") (pin "A") (pinfunction "A_A") (pintype "passive"))
      (node (ref "RL3") (pin "1") (pinfunction "1_1") (pintype "passive"))
    )
    (net (code "87") (name "Net-(LED11-PadA)") (class "Default")
      (node (ref "LED11") (pin "A") (pinfunction "A_A") (pintype "passive"))
      (node (ref "R14") (pin "1") (pinfunction "1_1") (pintype "passive"))
    )
    (net (code "88") (name "Net-(LED11-PadC)") (class "Default")
      (node (ref "LED11") (pin "C") (pinfunction "C_C") (pintype "passive"))
      (node (ref "U$3") (pin "NET") (pinfunction "NET_NET") (pintype "bidirectional"))
    )
    (net (code "89") (name "Net-(LED12-PadA)") (class "Default")
      (node (ref "LED12") (pin "A") (pinfunction "A_A") (pintype "passive"))
      (node (ref "R39") (pin "1") (pinfunction "1_1") (pintype "passive"))
    )
    (net (code "90") (name "Net-(LED12-PadC)") (class "Default")
      (node (ref "LED12") (pin "C") (pinfunction "C_C") (pintype "passive"))
      (node (ref "U$3") (pin "ALM") (pinfunction "ALM_ALM") (pintype "bidirectional"))
    )
    (net (code "91") (name "Net-(LED13-PadA)") (class "Default")
      (node (ref "LED13") (pin "A") (pinfunction "A_A") (pintype "passive"))
      (node (ref "RL1") (pin "2") (pinfunction "2_2") (pintype "passive"))
    )
    (net (code "92") (name "Net-(LED14-PadA)") (class "Default")
      (node (ref "LED14") (pin "A") (pinfunction "A_A") (pintype "passive"))
      (node (ref "RL7") (pin "2") (pinfunction "2_2") (pintype "passive"))
    )
    (net (code "93") (name "Net-(LED15-PadA)") (class "Default")
      (node (ref "LED15") (pin "A") (pinfunction "A_A") (pintype "passive"))
      (node (ref "RL9") (pin "1") (pinfunction "1_1") (pintype "passive"))
    )
    (net (code "94") (name "Net-(LED16-PadA)") (class "Default")
      (node (ref "LED16") (pin "A") (pinfunction "A_A") (pintype "passive"))
      (node (ref "R43") (pin "1") (pinfunction "1_1") (pintype "passive"))
    )
    (net (code "95") (name "Net-(Q7-G)") (class "Default")
      (node (ref "Q7") (pin "1") (pinfunction "G_1") (pintype "passive"))
      (node (ref "RL2") (pin "2") (pinfunction "2_2") (pintype "passive"))
    )
    (net (code "96") (name "Net-(R8-Pad2)") (class "Default")
      (node (ref "R8") (pin "2") (pinfunction "2_2") (pintype "passive"))
      (node (ref "U$3") (pin "TX1") (pinfunction "TX1_TX1") (pintype "bidirectional"))
    )
    (net (code "97") (name "Net-(R11-Pad2)") (class "Default")
      (node (ref "R11") (pin "2") (pinfunction "2_2") (pintype "passive"))
      (node (ref "U$3") (pin "RX1") (pinfunction "RX1_RX1") (pintype "bidirectional"))
    )
    (net (code "98") (name "Net-(R18-Pad2)") (class "Default")
      (node (ref "R18") (pin "2") (pinfunction "2_2") (pintype "passive"))
      (node (ref "U$1") (pin "SCK") (pinfunction "SCK_SCK") (pintype "bidirectional"))
    )
    (net (code "99") (name "Net-(R24-Pad2)") (class "Default")
      (node (ref "R24") (pin "2") (pinfunction "2_2") (pintype "passive"))
      (node (ref "X4") (pin "3") (pinfunction "3_3") (pintype "passive"))
    )
    (net (code "100") (name "Net-(R31-Pad2)") (class "Default")
      (node (ref "R31") (pin "2") (pinfunction "2_2") (pintype "passive"))
      (node (ref "X4") (pin "2") (pinfunction "2_2") (pintype "passive"))
    )
    (net (code "101") (name "Net-(R44-PadS)") (class "Default")
      (node (ref "R44") (pin "S") (pinfunction "S_S") (pintype "passive"))
      (node (ref "U$12") (pin "3") (pinfunction "3_3") (pintype "passive"))
    )
    (net (code "102") (name "Net-(U$1-CS)") (class "Default")
      (node (ref "R16") (pin "1") (pinfunction "1_1") (pintype "passive"))
      (node (ref "R17") (pin "1") (pinfunction "1_1") (pintype "passive"))
      (node (ref "U$1") (pin "CE") (pinfunction "CS_CE") (pintype "bidirectional"))
    )
    (net (code "103") (name "Net-(U$4-UCAP)") (class "Default")
      (node (ref "C3") (pin "2") (pinfunction "2_2") (pintype "passive"))
      (node (ref "U$4") (pin "6") (pinfunction "UCAP_6") (pintype "bidirectional"))
    )
    (net (code "104") (name "Net-(X1B-S)") (class "Default")
      (node (ref "R20") (pin "2") (pinfunction "2_2") (pintype "passive"))
      (node (ref "X1") (pin "2") (pinfunction "S_2") (pintype "passive"))
    )
    (net (code "105") (name "Net-(X1C-S)") (class "Default")
      (node (ref "R19") (pin "2") (pinfunction "2_2") (pintype "passive"))
      (node (ref "X1") (pin "3") (pinfunction "S_3") (pintype "passive"))
    )
    (net (code "106") (name "Net-(X2B-S)") (class "Default")
      (node (ref "R10") (pin "2") (pinfunction "2_2") (pintype "passive"))
      (node (ref "RL6") (pin "2") (pinfunction "2_2") (pintype "passive"))
      (node (ref "X2") (pin "2") (pinfunction "S_2") (pintype "passive"))
    )
    (net (code "107") (name "Net-(X5B-S)") (class "Default")
      (node (ref "R21") (pin "2") (pinfunction "2_2") (pintype "passive"))
      (node (ref "RL8") (pin "2") (pinfunction "2_2") (pintype "passive"))
      (node (ref "X5") (pin "2") (pinfunction "S_2") (pintype "passive"))
    )
    (net (code "108") (name "VUSB") (class "Default")
      (node (ref "C7") (pin "2") (pinfunction "2_2") (pintype "passive"))
      (node (ref "D4") (pin "A") (pinfunction "A_A") (pintype "passive"))
      (node (ref "U$4") (pin "7") (pinfunction "VBUS_7") (pintype "bidirectional"))
      (node (ref "X4") (pin "1") (pinfunction "1_1") (pintype "passive"))
    )
    (net (code "109") (name "unconnected-(CFG-Pad2)") (class "Default")
      (node (ref "CFG") (pin "2") (pinfunction "2_2") (pintype "passive"))
    )
    (net (code "110") (name "unconnected-(CFG-Pad3)") (class "Default")
      (node (ref "CFG") (pin "3") (pinfunction "3_3") (pintype "passive"))
    )
    (net (code "111") (name "unconnected-(I/O_PWM-1-Pad+12V)") (class "Default")
      (node (ref "I/O_PWM") (pin "+12V") (pinfunction "1_+12V") (pintype "bidirectional"))
    )
    (net (code "112") (name "unconnected-(I/O_PWM-6-PadGND1)") (class "Default")
      (node (ref "I/O_PWM") (pin "GND1") (pinfunction "6_GND1") (pintype "bidirectional"))
    )
    (net (code "113") (name "unconnected-(J6-1-Pad+12V)") (class "Default")
      (node (ref "J6") (pin "+12V") (pinfunction "1_+12V") (pintype "bidirectional"))
    )
    (net (code "114") (name "unconnected-(J8-1-Pad+12V)") (class "Default")
      (node (ref "J8") (pin "+12V") (pinfunction "1_+12V") (pintype "bidirectional"))
    )
    (net (code "115") (name "unconnected-(Q1-D-Pad4)") (class "Default")
      (node (ref "Q1") (pin "4") (pinfunction "D_4") (pintype "passive"))
    )
    (net (code "116") (name "unconnected-(Q2-D-Pad4)") (class "Default")
      (node (ref "Q2") (pin "4") (pinfunction "D_4") (pintype "passive"))
    )
    (net (code "117") (name "unconnected-(Q3-D-Pad4)") (class "Default")
      (node (ref "Q3") (pin "4") (pinfunction "D_4") (pintype "passive"))
    )
    (net (code "118") (name "unconnected-(Q4-D-Pad4)") (class "Default")
      (node (ref "Q4") (pin "4") (pinfunction "D_4") (pintype "passive"))
    )
    (net (code "119") (name "unconnected-(Q5-D-Pad4)") (class "Default")
      (node (ref "Q5") (pin "4") (pinfunction "D_4") (pintype "passive"))
    )
    (net (code "120") (name "unconnected-(Q6-D-Pad4)") (class "Default")
      (node (ref "Q6") (pin "4") (pinfunction "D_4") (pintype "passive"))
    )
    (net (code "121") (name "unconnected-(RESET1-Pad1)") (class "Default")
      (node (ref "RESET1") (pin "1") (pinfunction "1_1") (pintype "passive"))
    )
    (net (code "122") (name "unconnected-(RESET1-Pad3)") (class "Default")
      (node (ref "RESET1") (pin "3") (pinfunction "3_3") (pintype "passive"))
    )
    (net (code "123") (name "unconnected-(U$3-PadRST)") (class "Default")
      (node (ref "U$3") (pin "RST") (pinfunction "RST_RST") (pintype "bidirectional"))
    )
    (net (code "124") (name "unconnected-(U$10-Pad1)") (class "Default")
      (node (ref "U$10") (pin "1") (pinfunction "1_1") (pintype "passive"))
    )
    (net (code "125") (name "unconnected-(U$10-Pad2)") (class "Default")
      (node (ref "U$10") (pin "2") (pinfunction "2_2") (pintype "passive"))
    )
    (net (code "126") (name "unconnected-(U$10-Pad3)") (class "Default")
      (node (ref "U$10") (pin "3") (pinfunction "3_3") (pintype "passive"))
    )
    (net (code "127") (name "unconnected-(U$10-Pad4)") (class "Default")
      (node (ref "U$10") (pin "4") (pinfunction "4_4") (pintype "passive"))
    )
    (net (code "128") (name "unconnected-(U$10-Pad5)") (class "Default")
      (node (ref "U$10") (pin "5") (pinfunction "5_5") (pintype "passive"))
    )
    (net (code "129") (name "unconnected-(U$10-Pad6)") (class "Default")
      (node (ref "U$10") (pin "6") (pinfunction "6_6") (pintype "passive"))
    )
    (net (code "130") (name "unconnected-(U$10-Pad7)") (class "Default")
      (node (ref "U$10") (pin "7") (pinfunction "7_7") (pintype "passive"))
    )
    (net (code "131") (name "unconnected-(U$10-Pad8)") (class "Default")
      (node (ref "U$10") (pin "8") (pinfunction "8_8") (pintype "passive"))
    )
    (net (code "132") (name "unconnected-(U$10-Pad9)") (class "Default")
      (node (ref "U$10") (pin "9") (pinfunction "9_9") (pintype "passive"))
    )
    (net (code "133") (name "unconnected-(U$10-Pad10)") (class "Default")
      (node (ref "U$10") (pin "10") (pinfunction "10_10") (pintype "passive"))
    )
    (net (code "134") (name "unconnected-(U$10-Pad11)") (class "Default")
      (node (ref "U$10") (pin "11") (pinfunction "11_11") (pintype "passive"))
    )
    (net (code "135") (name "unconnected-(U$10-Pad12)") (class "Default")
      (node (ref "U$10") (pin "12") (pinfunction "12_12") (pintype "passive"))
    )
    (net (code "136") (name "unconnected-(U$10-Pad13)") (class "Default")
      (node (ref "U$10") (pin "13") (pinfunction "13_13") (pintype "passive"))
    )
    (net (code "137") (name "unconnected-(U$10-Pad14)") (class "Default")
      (node (ref "U$10") (pin "14") (pinfunction "14_14") (pintype "passive"))
    )
    (net (code "138") (name "unconnected-(U$10-Pad15)") (class "Default")
      (node (ref "U$10") (pin "15") (pinfunction "15_15") (pintype "passive"))
    )
    (net (code "139") (name "unconnected-(U$10-Pad16)") (class "Default")
      (node (ref "U$10") (pin "16") (pinfunction "16_16") (pintype "passive"))
    )
    (net (code "140") (name "unconnected-(U$12-Pad4)") (class "Default")
      (node (ref "U$12") (pin "4") (pinfunction "4_4") (pintype "passive"))
    )
    (net (code "141") (name "unconnected-(U$12-Pad6)") (class "Default")
      (node (ref "U$12") (pin "6") (pinfunction "6_6") (pintype "passive"))
    )
    (net (code "142") (name "unconnected-(U$12-Pad11)") (class "Default")
      (node (ref "U$12") (pin "11") (pinfunction "11_11") (pintype "passive"))
    )
    (net (code "143") (name "unconnected-(U$12-Pad12)") (class "Default")
      (node (ref "U$12") (pin "12") (pinfunction "12_12") (pintype "passive"))
    )
    (net (code "144") (name "unconnected-(U$12-Pad13)") (class "Default")
      (node (ref "U$12") (pin "13") (pinfunction "13_13") (pintype "passive"))
    )
    (net (code "145") (name "unconnected-(U$12-Pad14)") (class "Default")
      (node (ref "U$12") (pin "14") (pinfunction "14_14") (pintype "passive"))
    )
    (net (code "146") (name "unconnected-(X4-Pad4)") (class "Default")
      (node (ref "X4") (pin "4") (pinfunction "4_4") (pintype "passive"))
    )
  )
)
